# SCH_Solenoid_Door_Lock_using_EM-18_2023-.net
KiCad netlist of a schematic drawn in EasyEDA
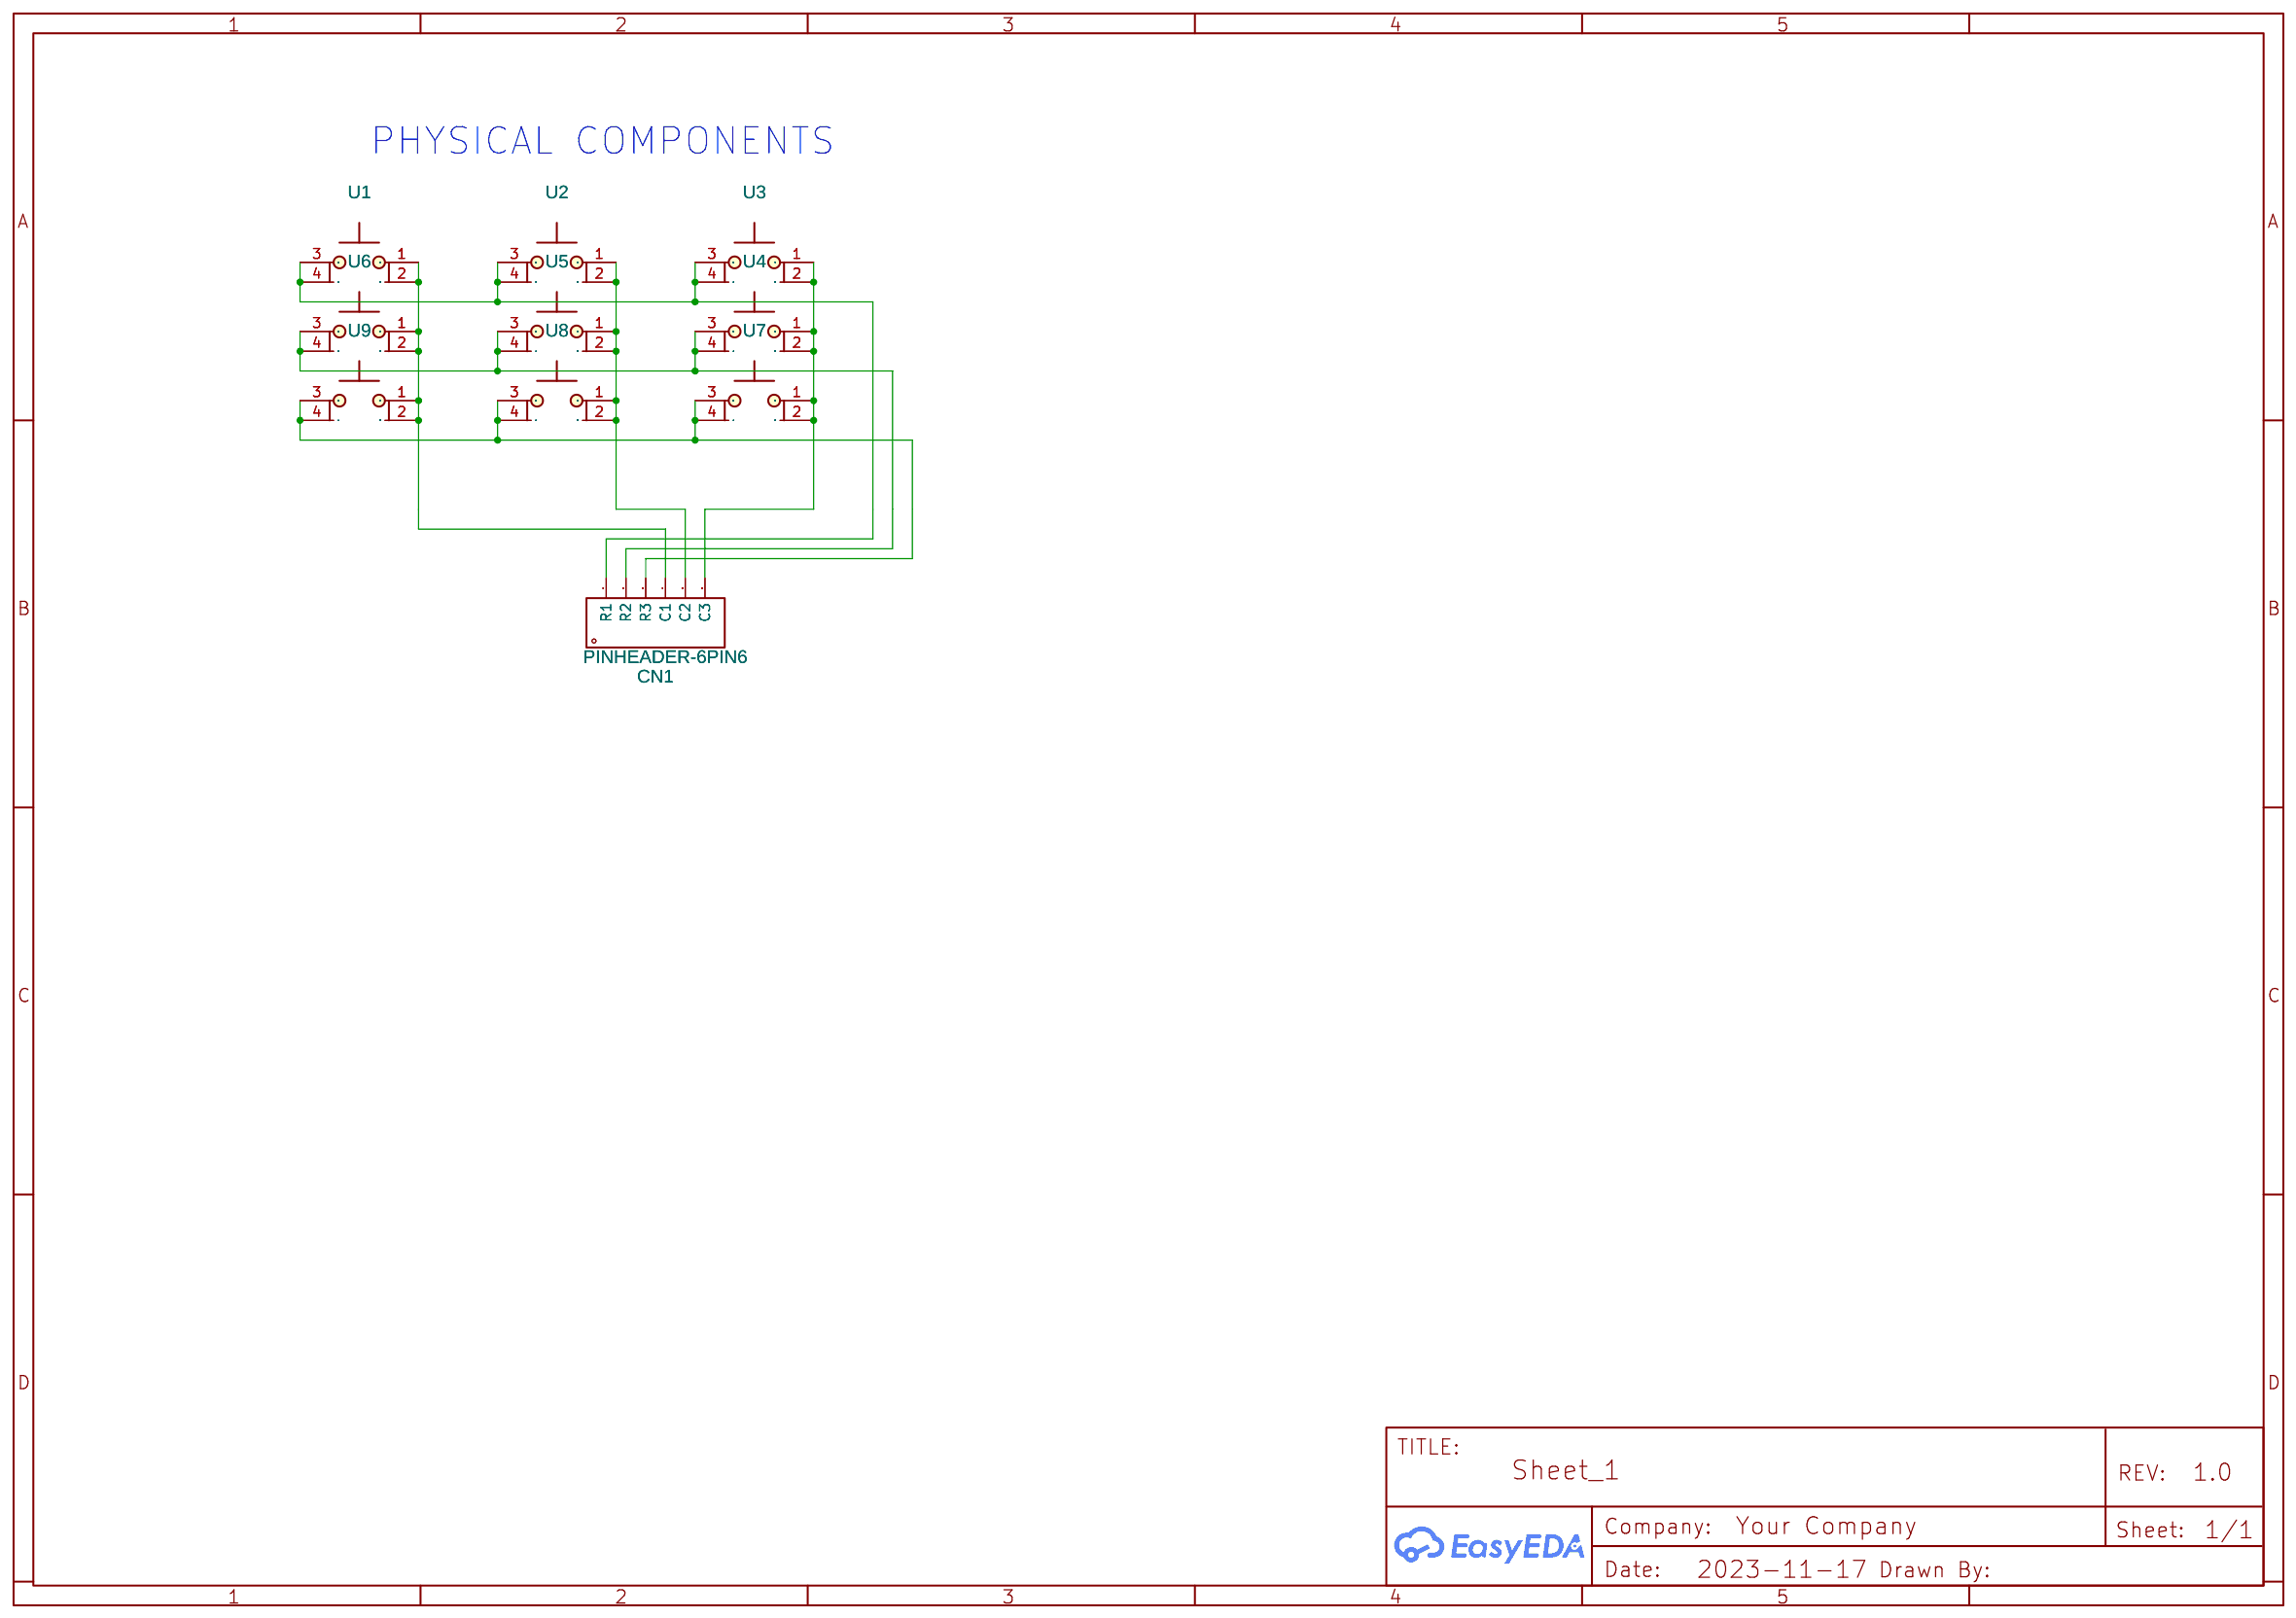
[diagram p0: 3x3 KeyPad]
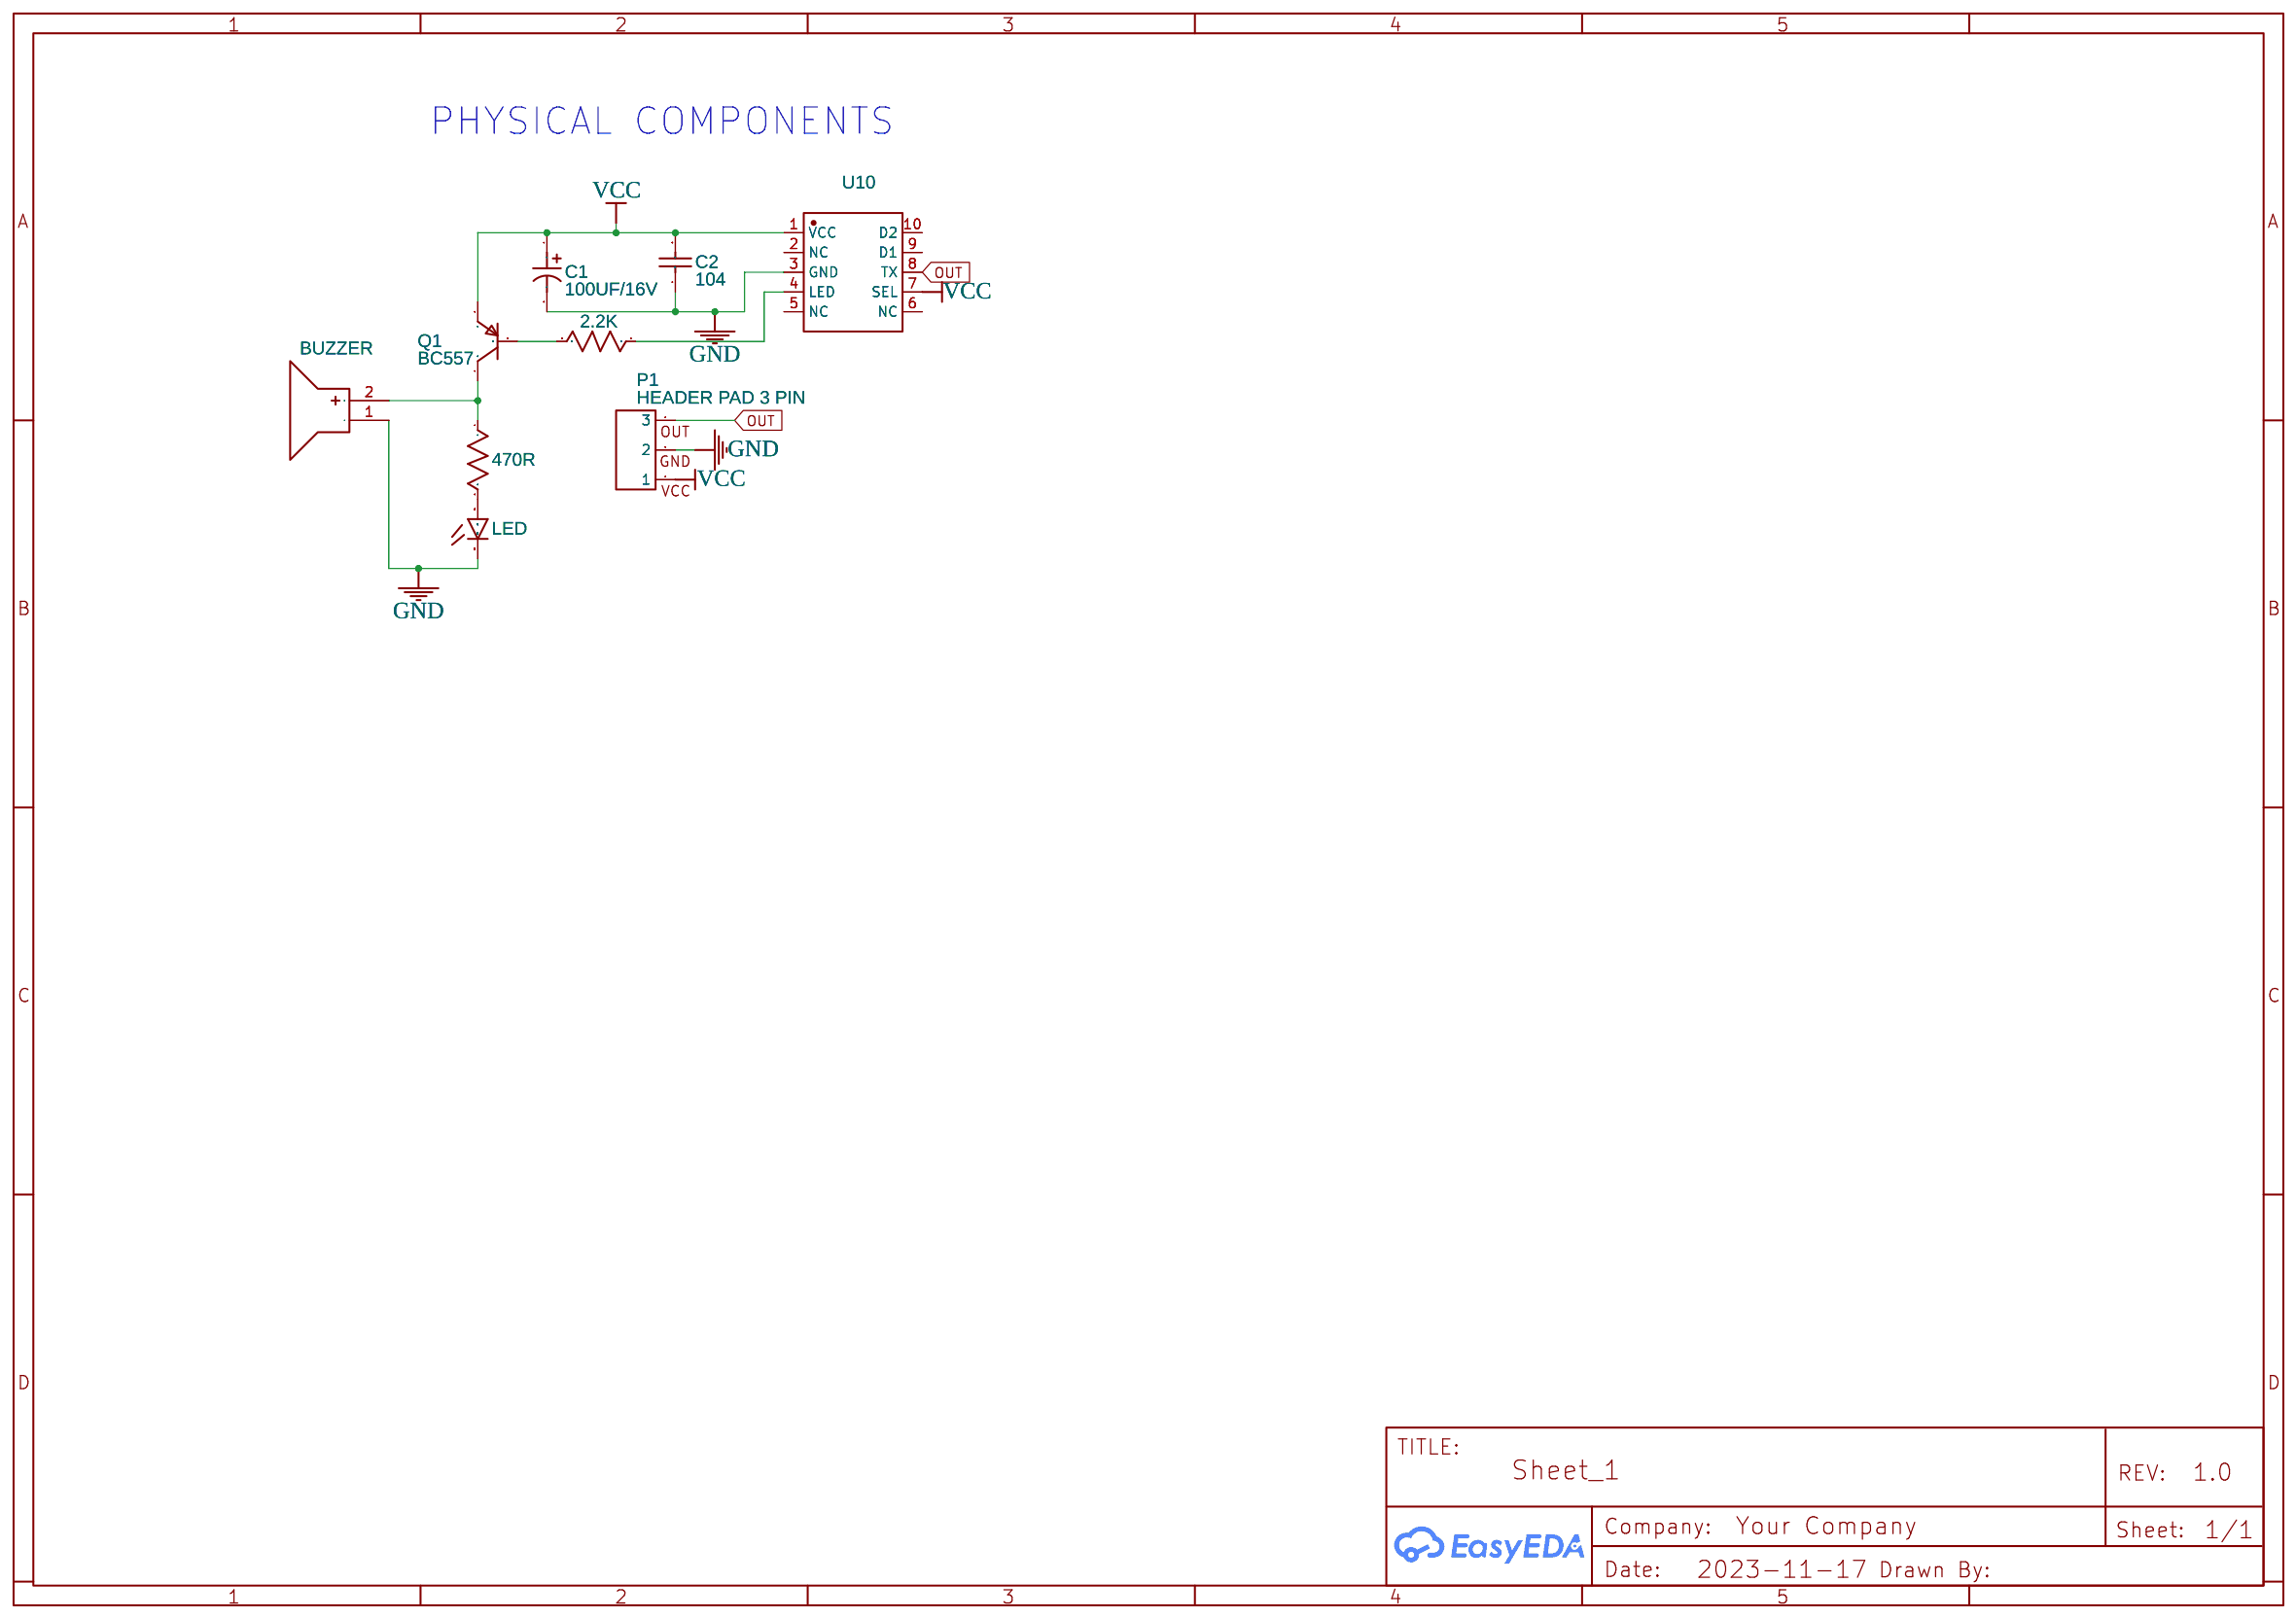
[diagram p1: EM-18 Module]
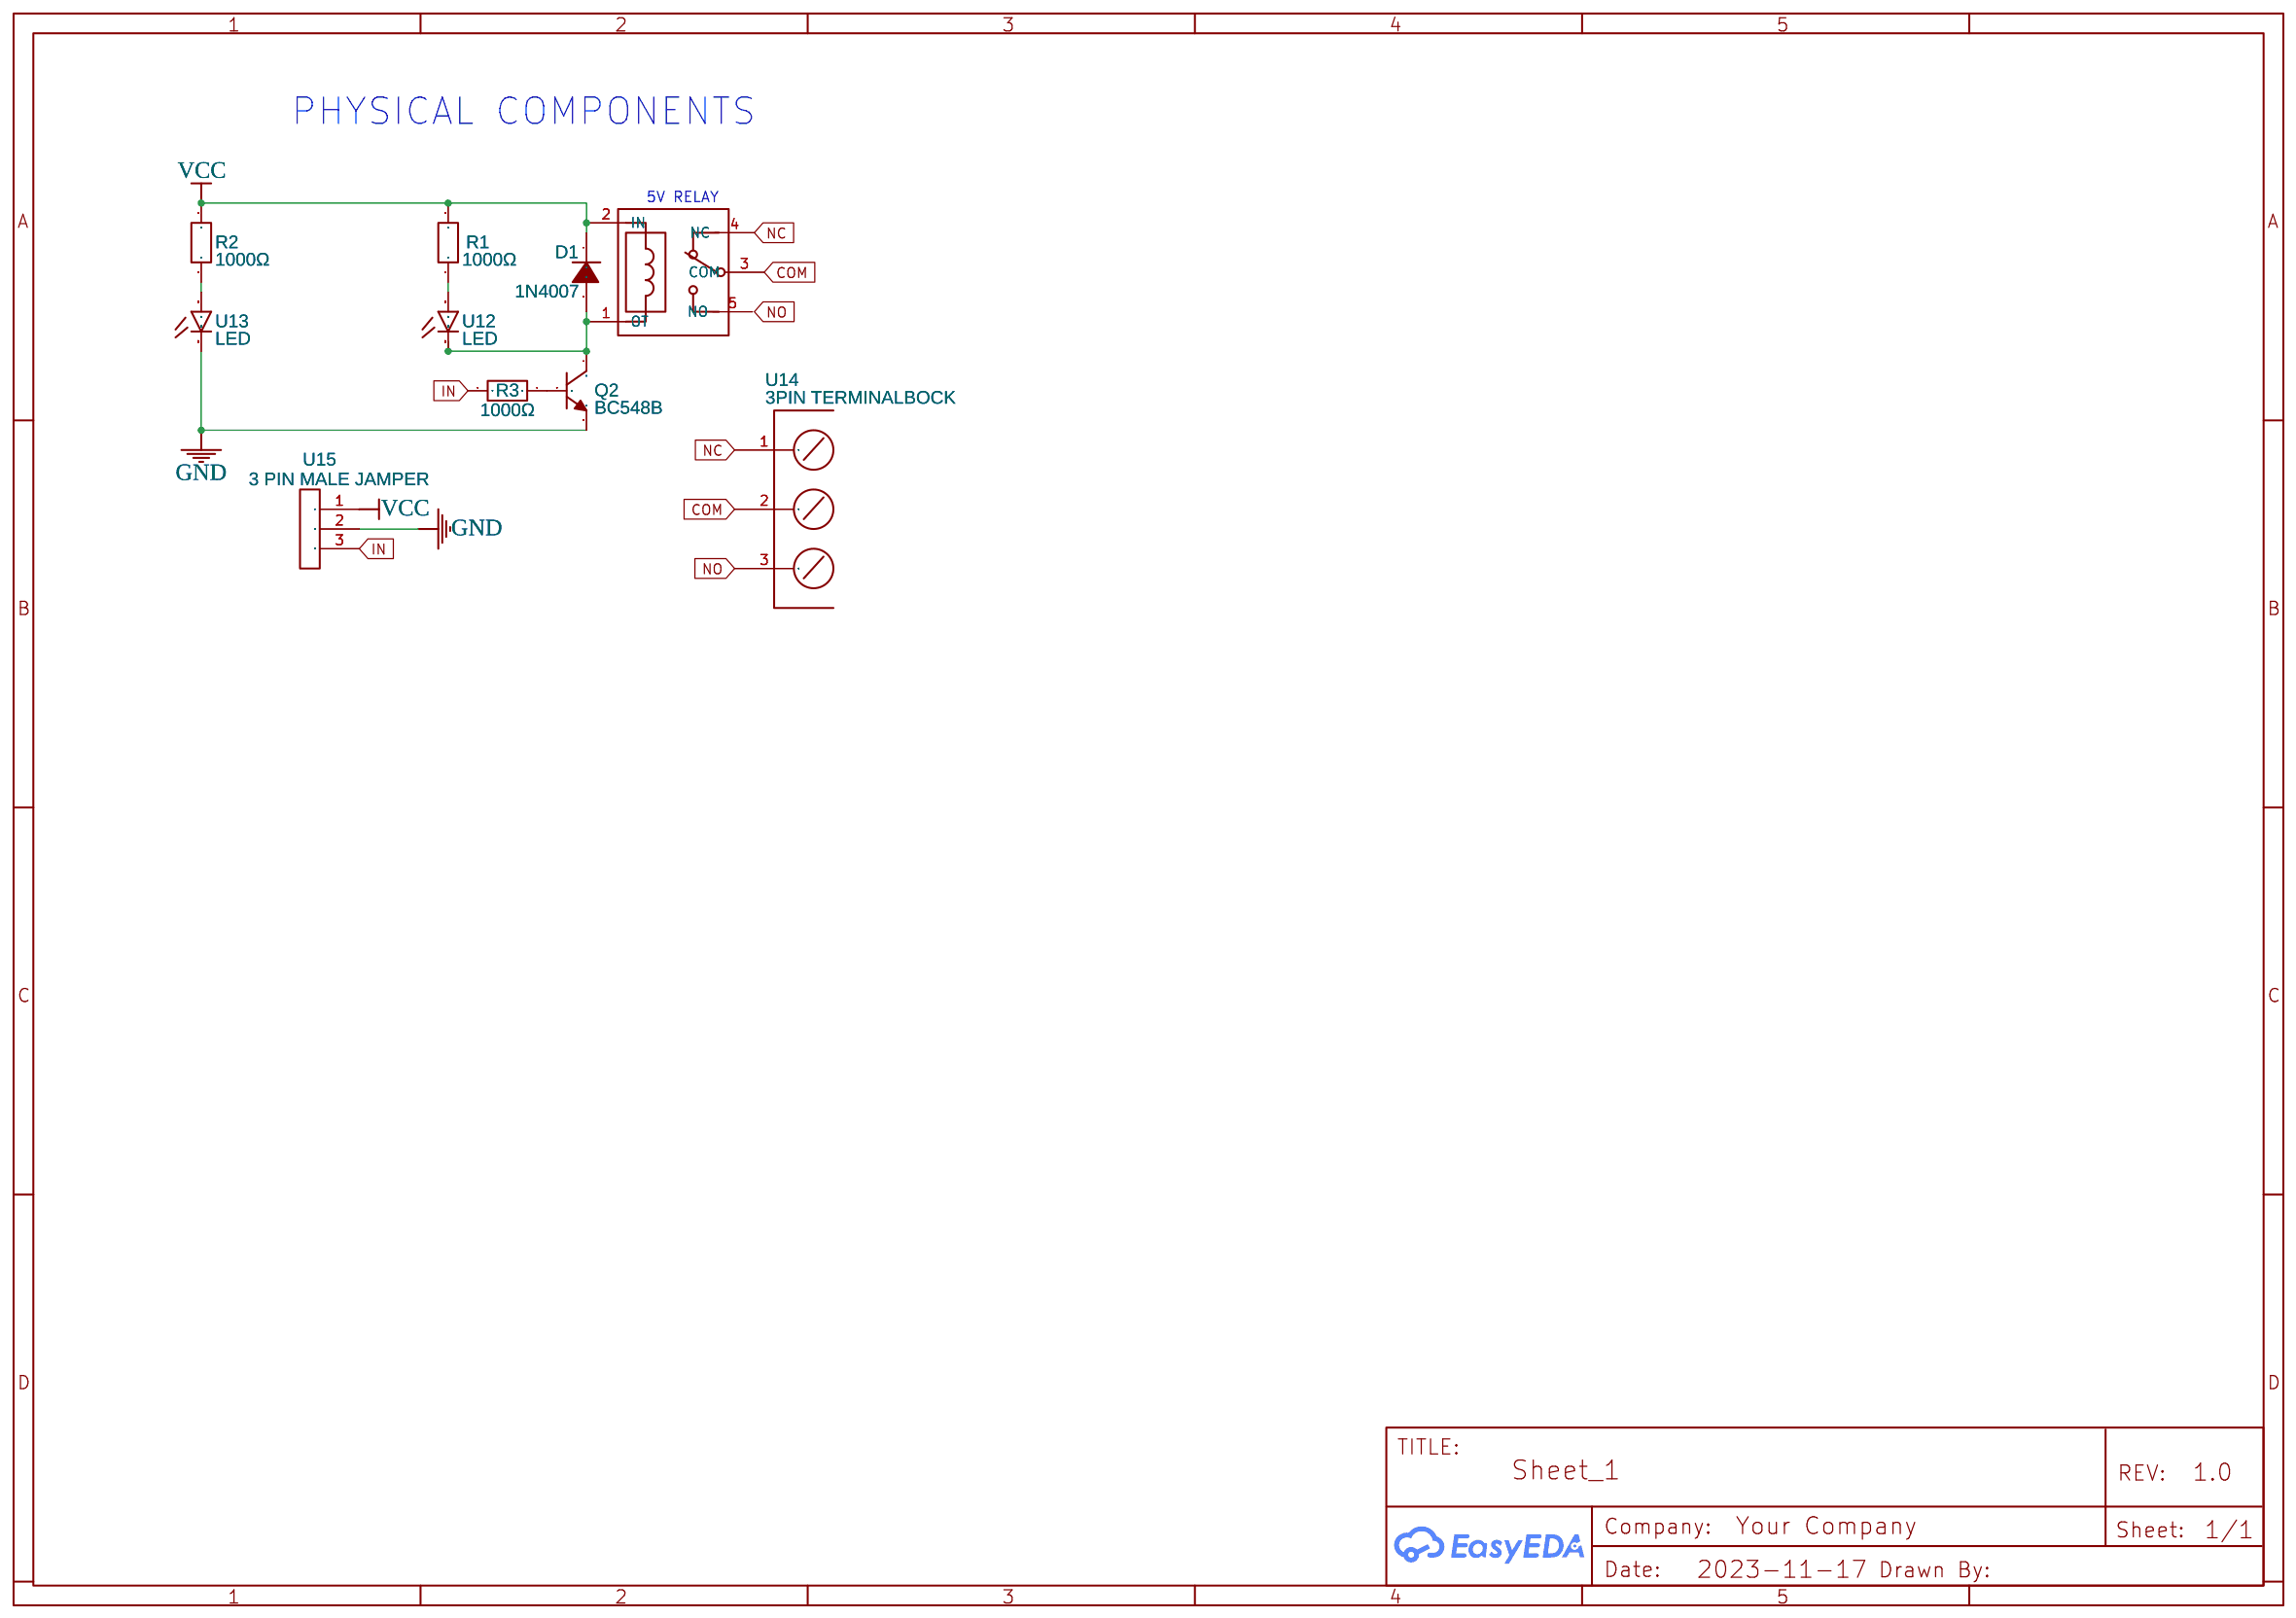
[diagram p2: Relay Module]
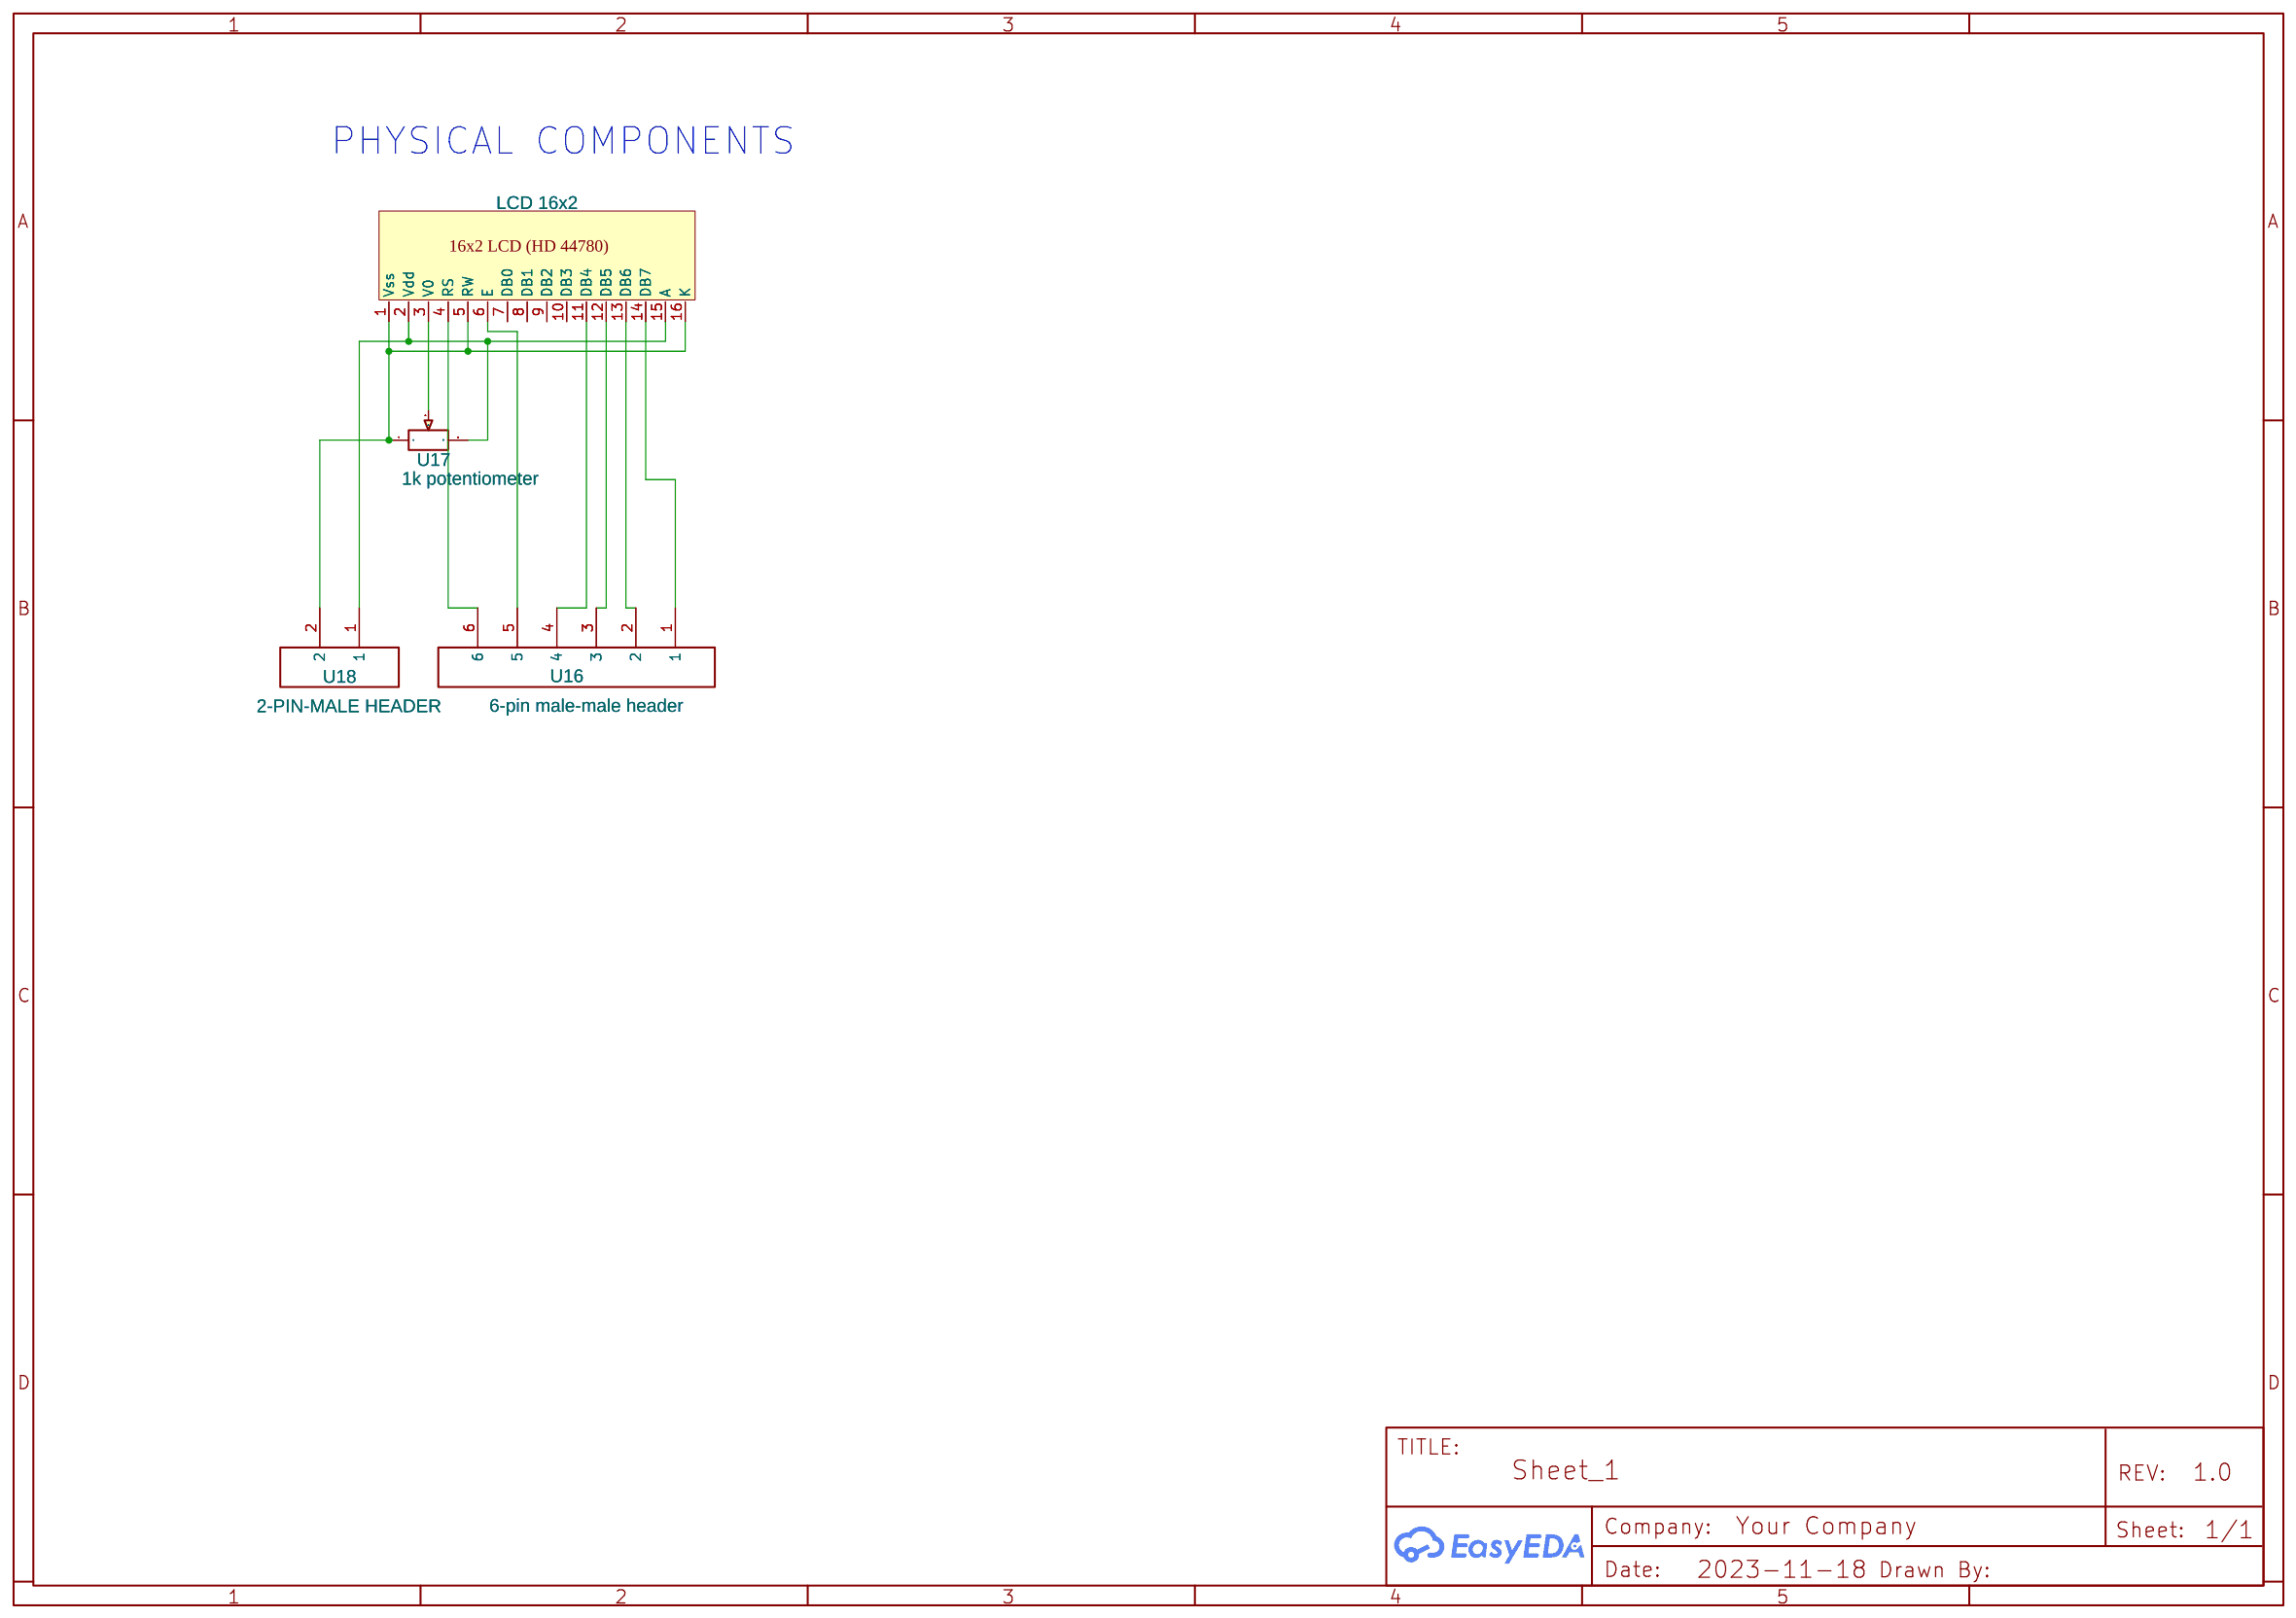
[diagram p3: LCD Display]
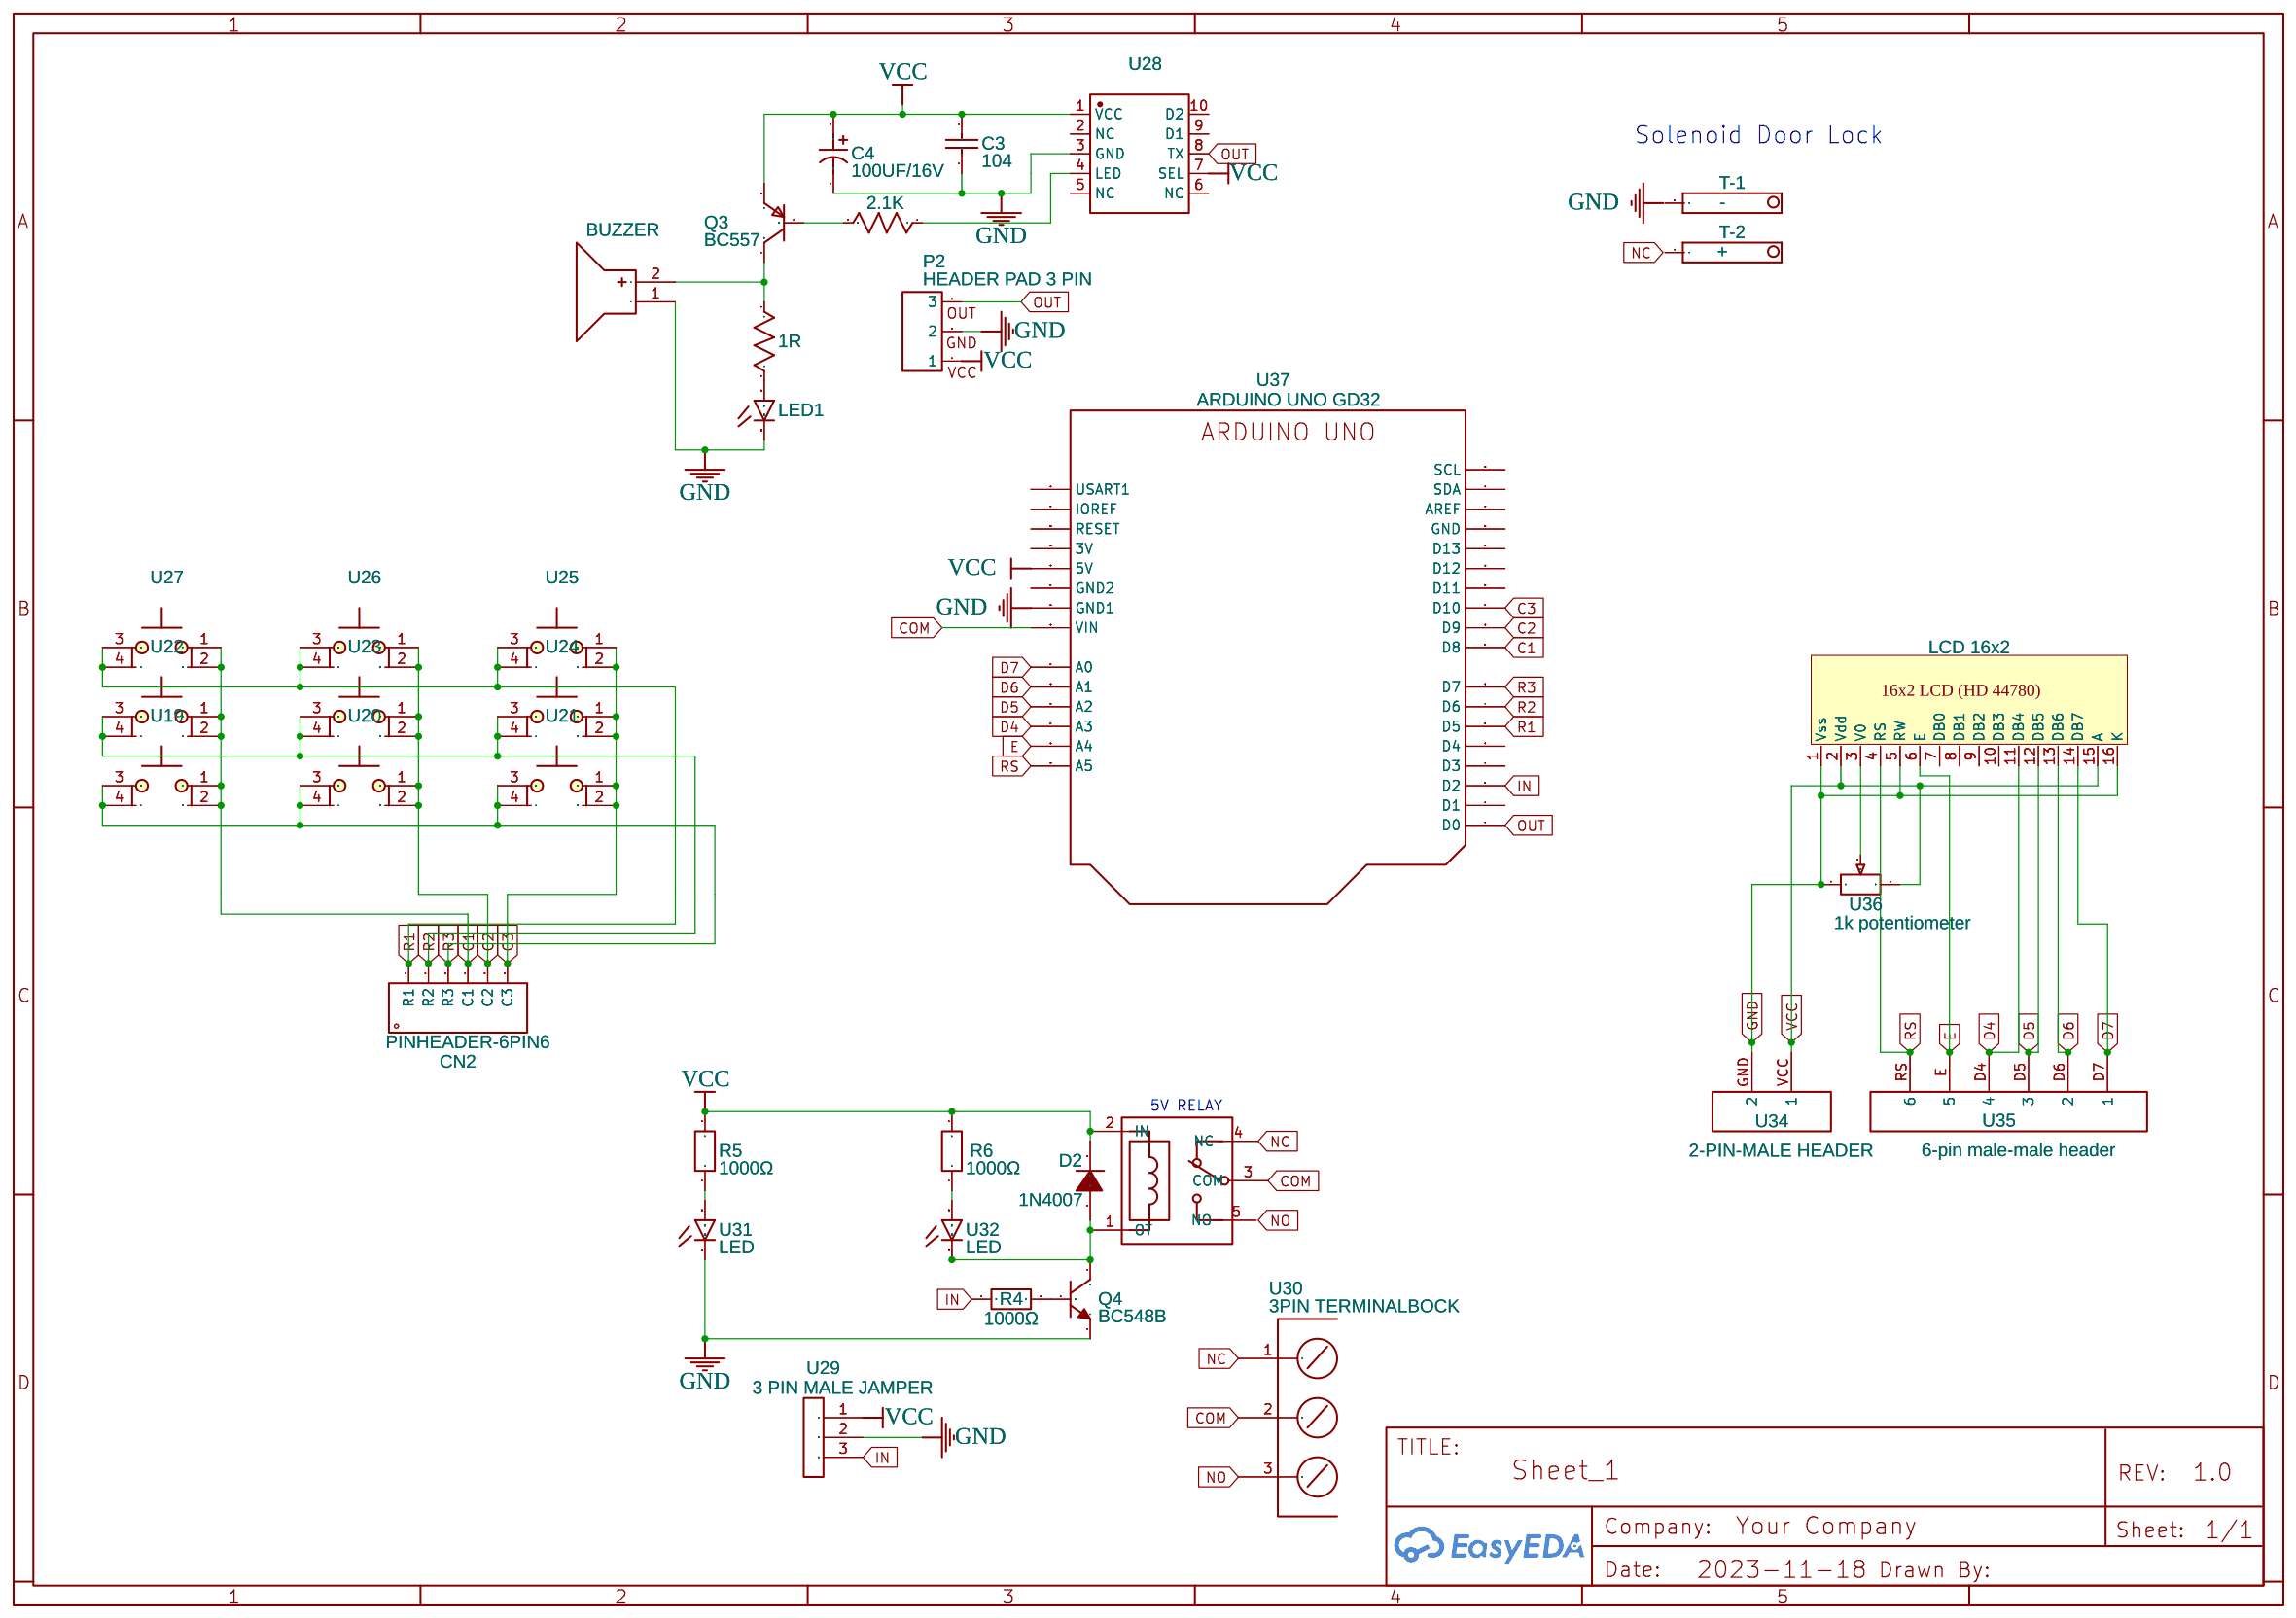
[diagram p4: Final Display]
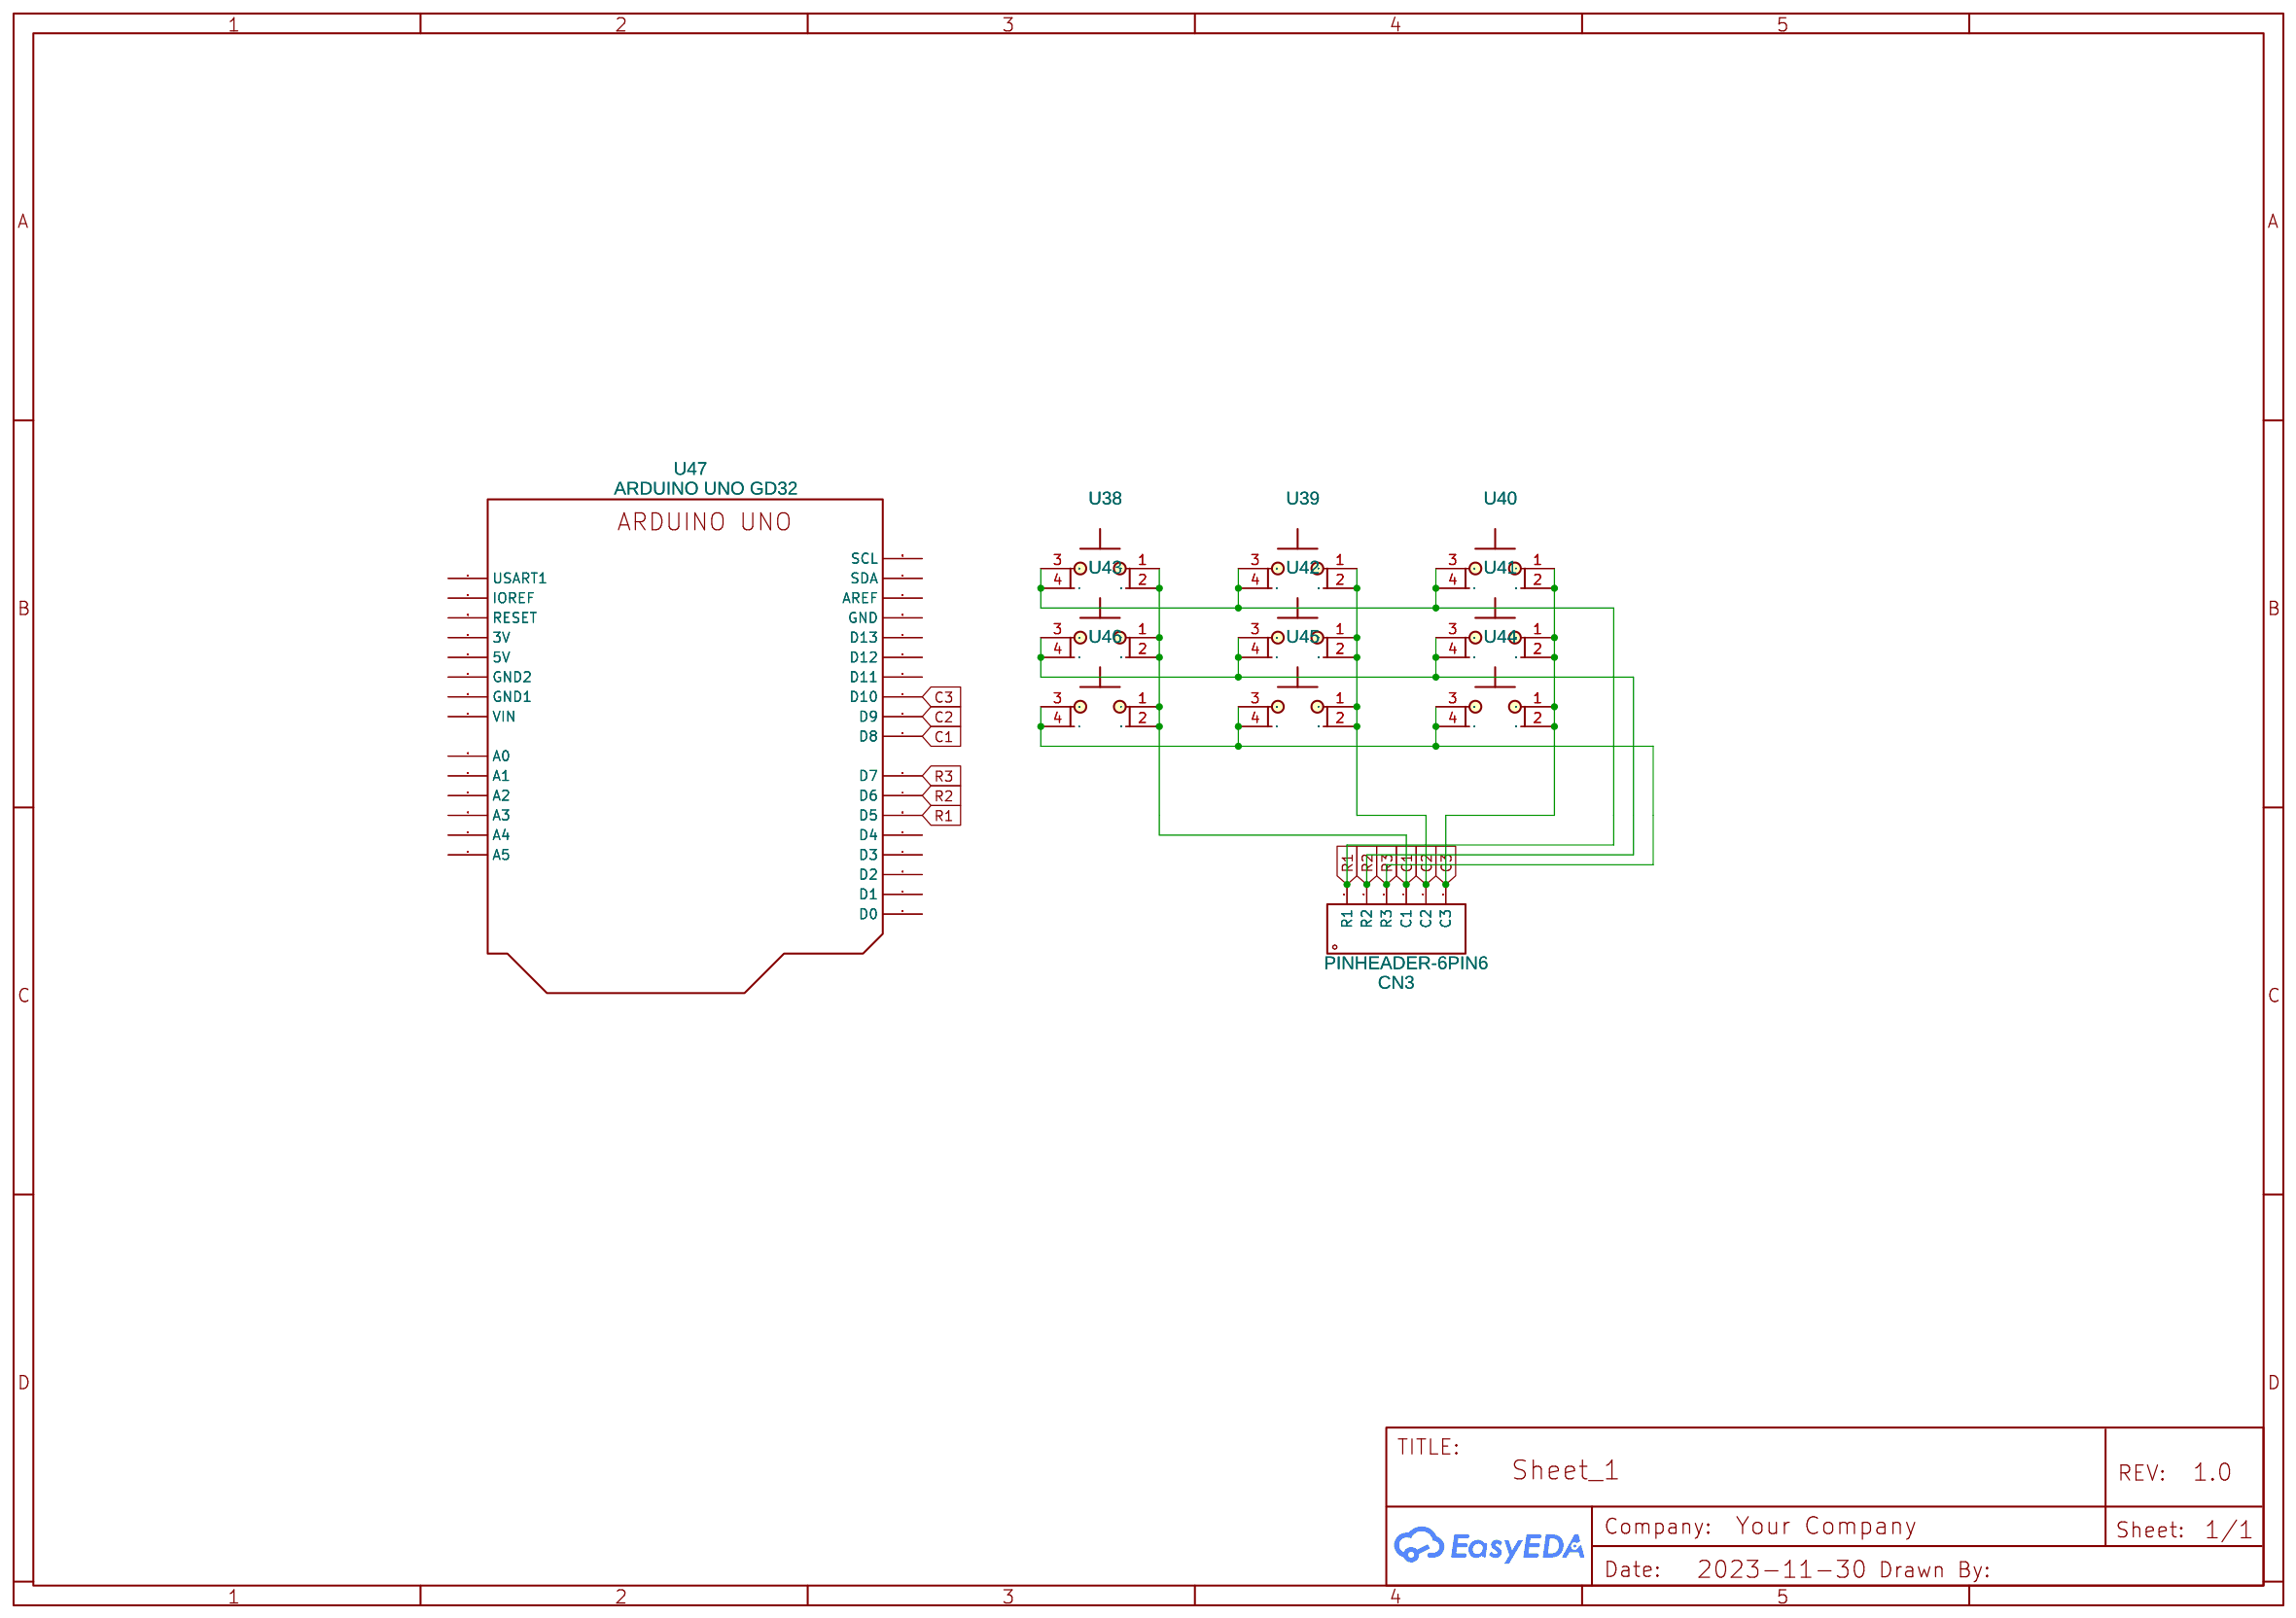
[diagram p5: Arduino_Keypad]
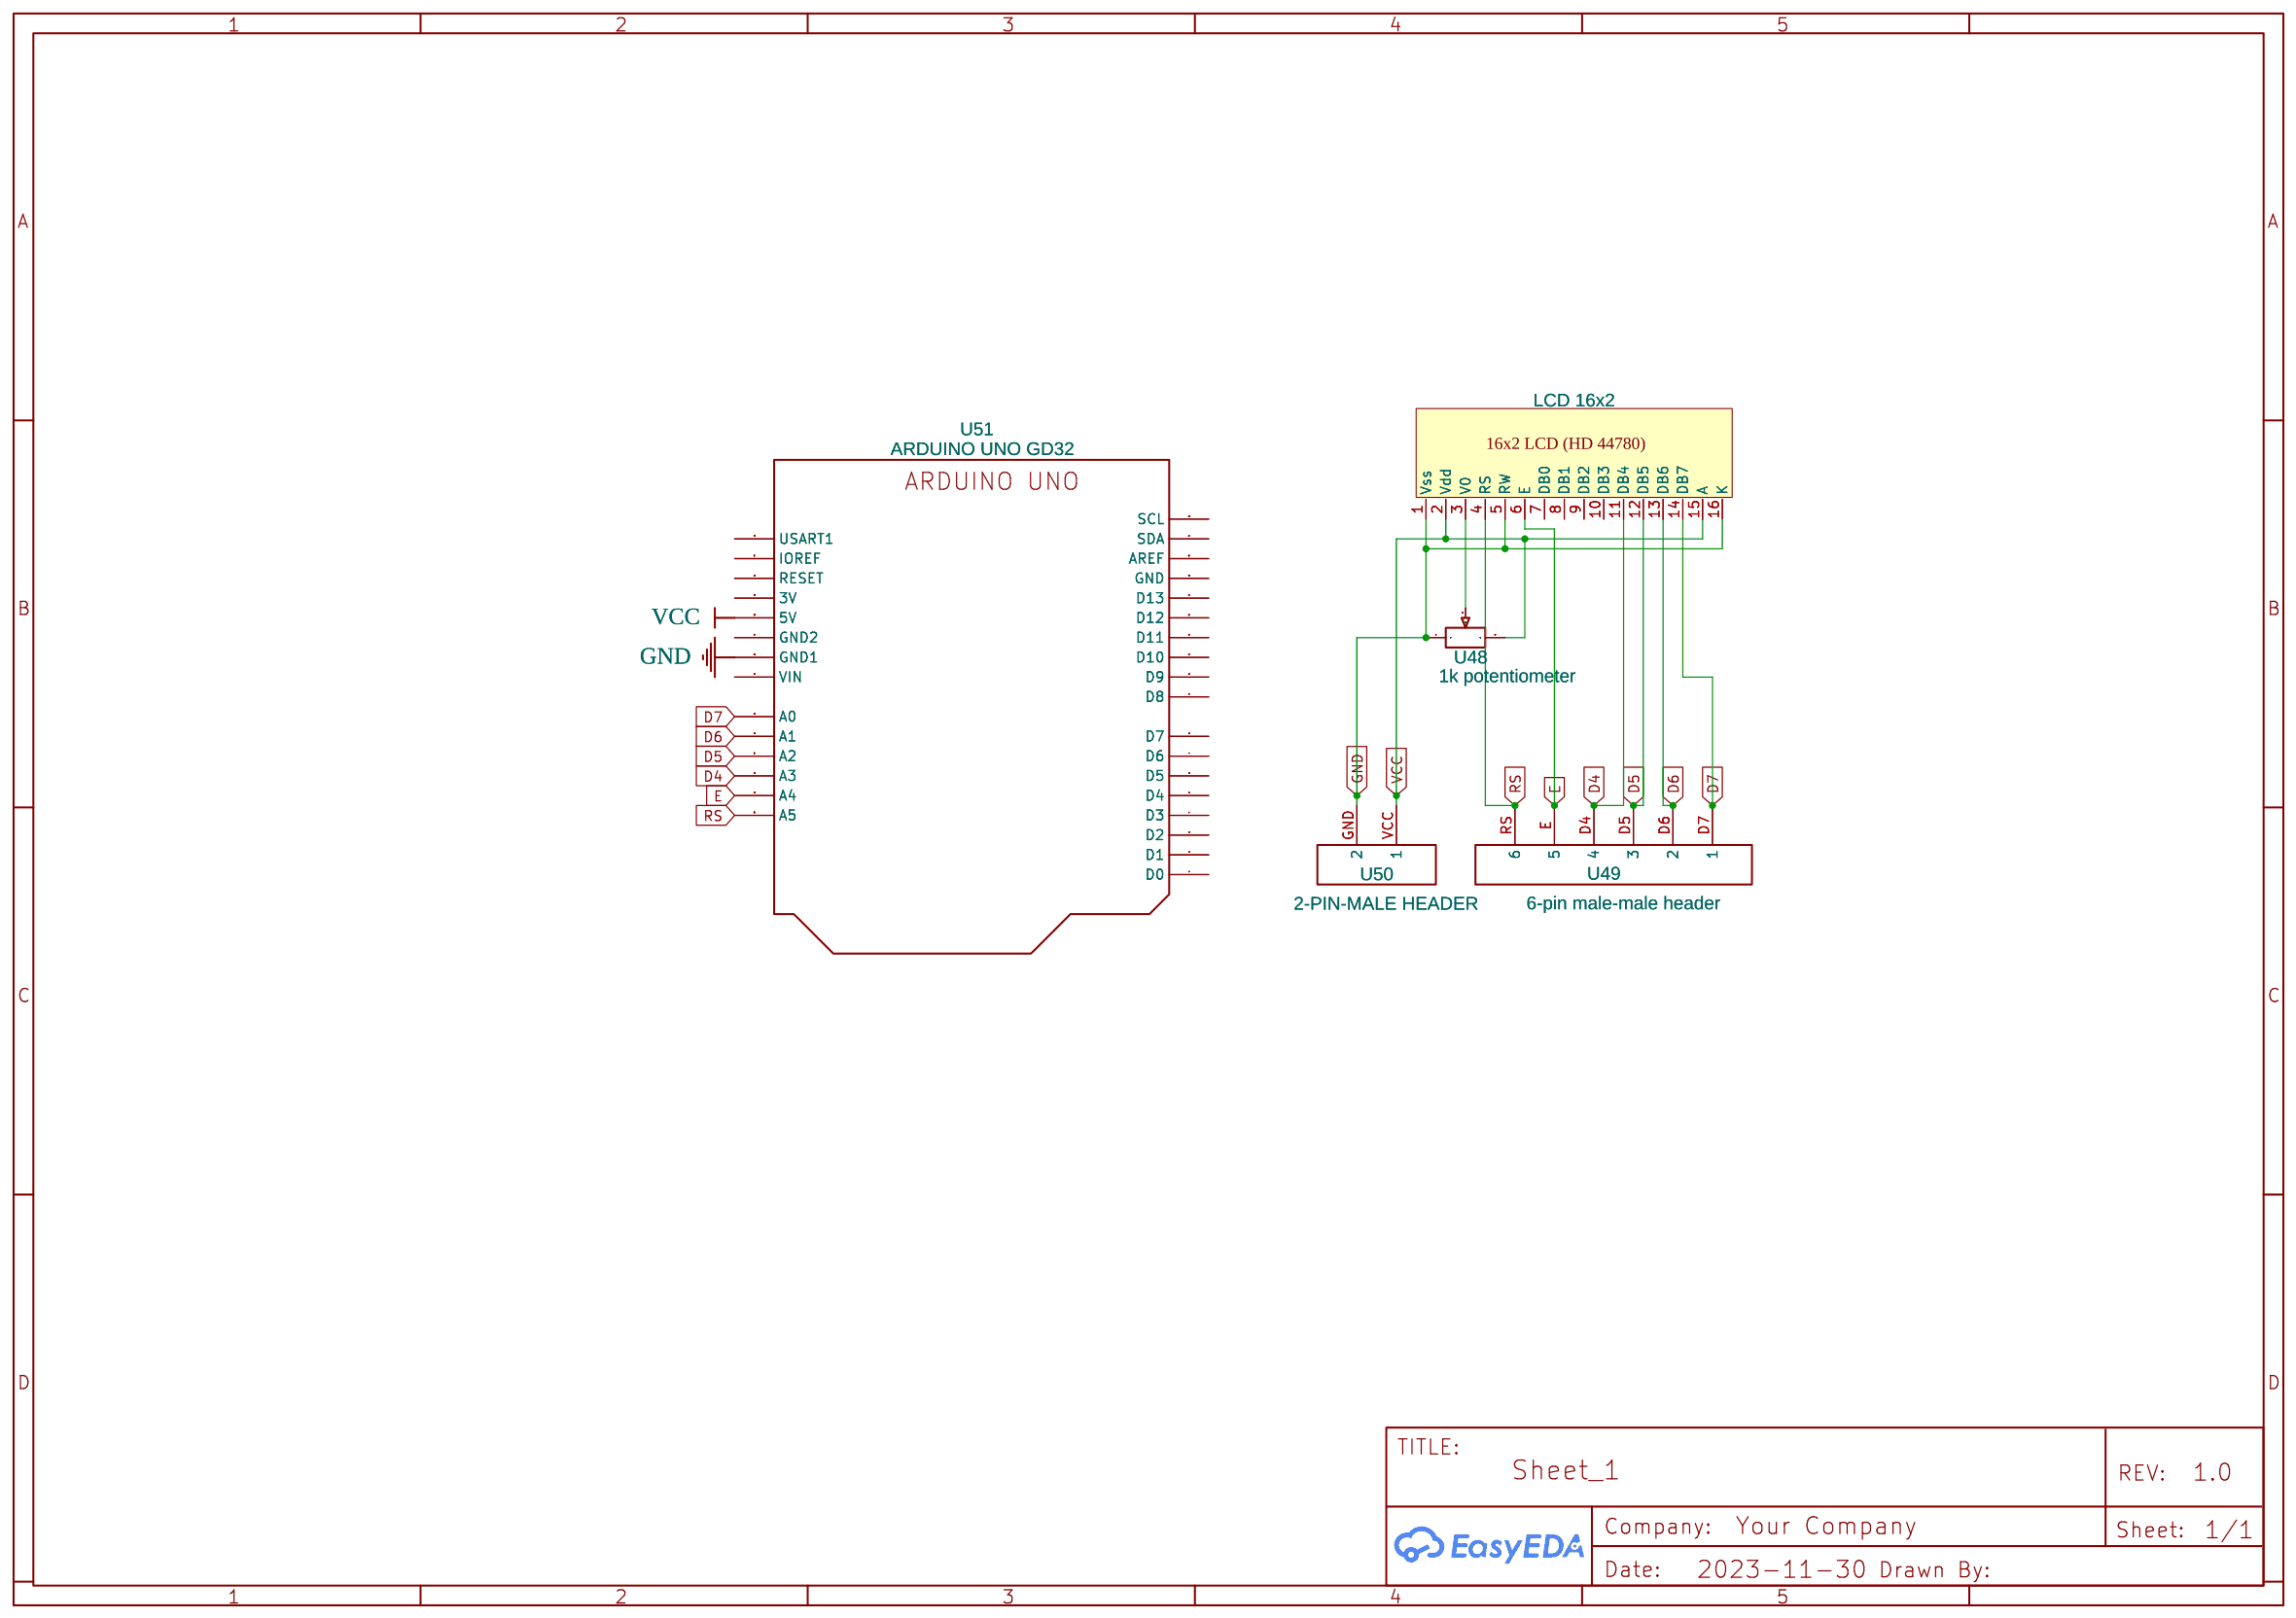
[diagram p6: Arduino_LCD]
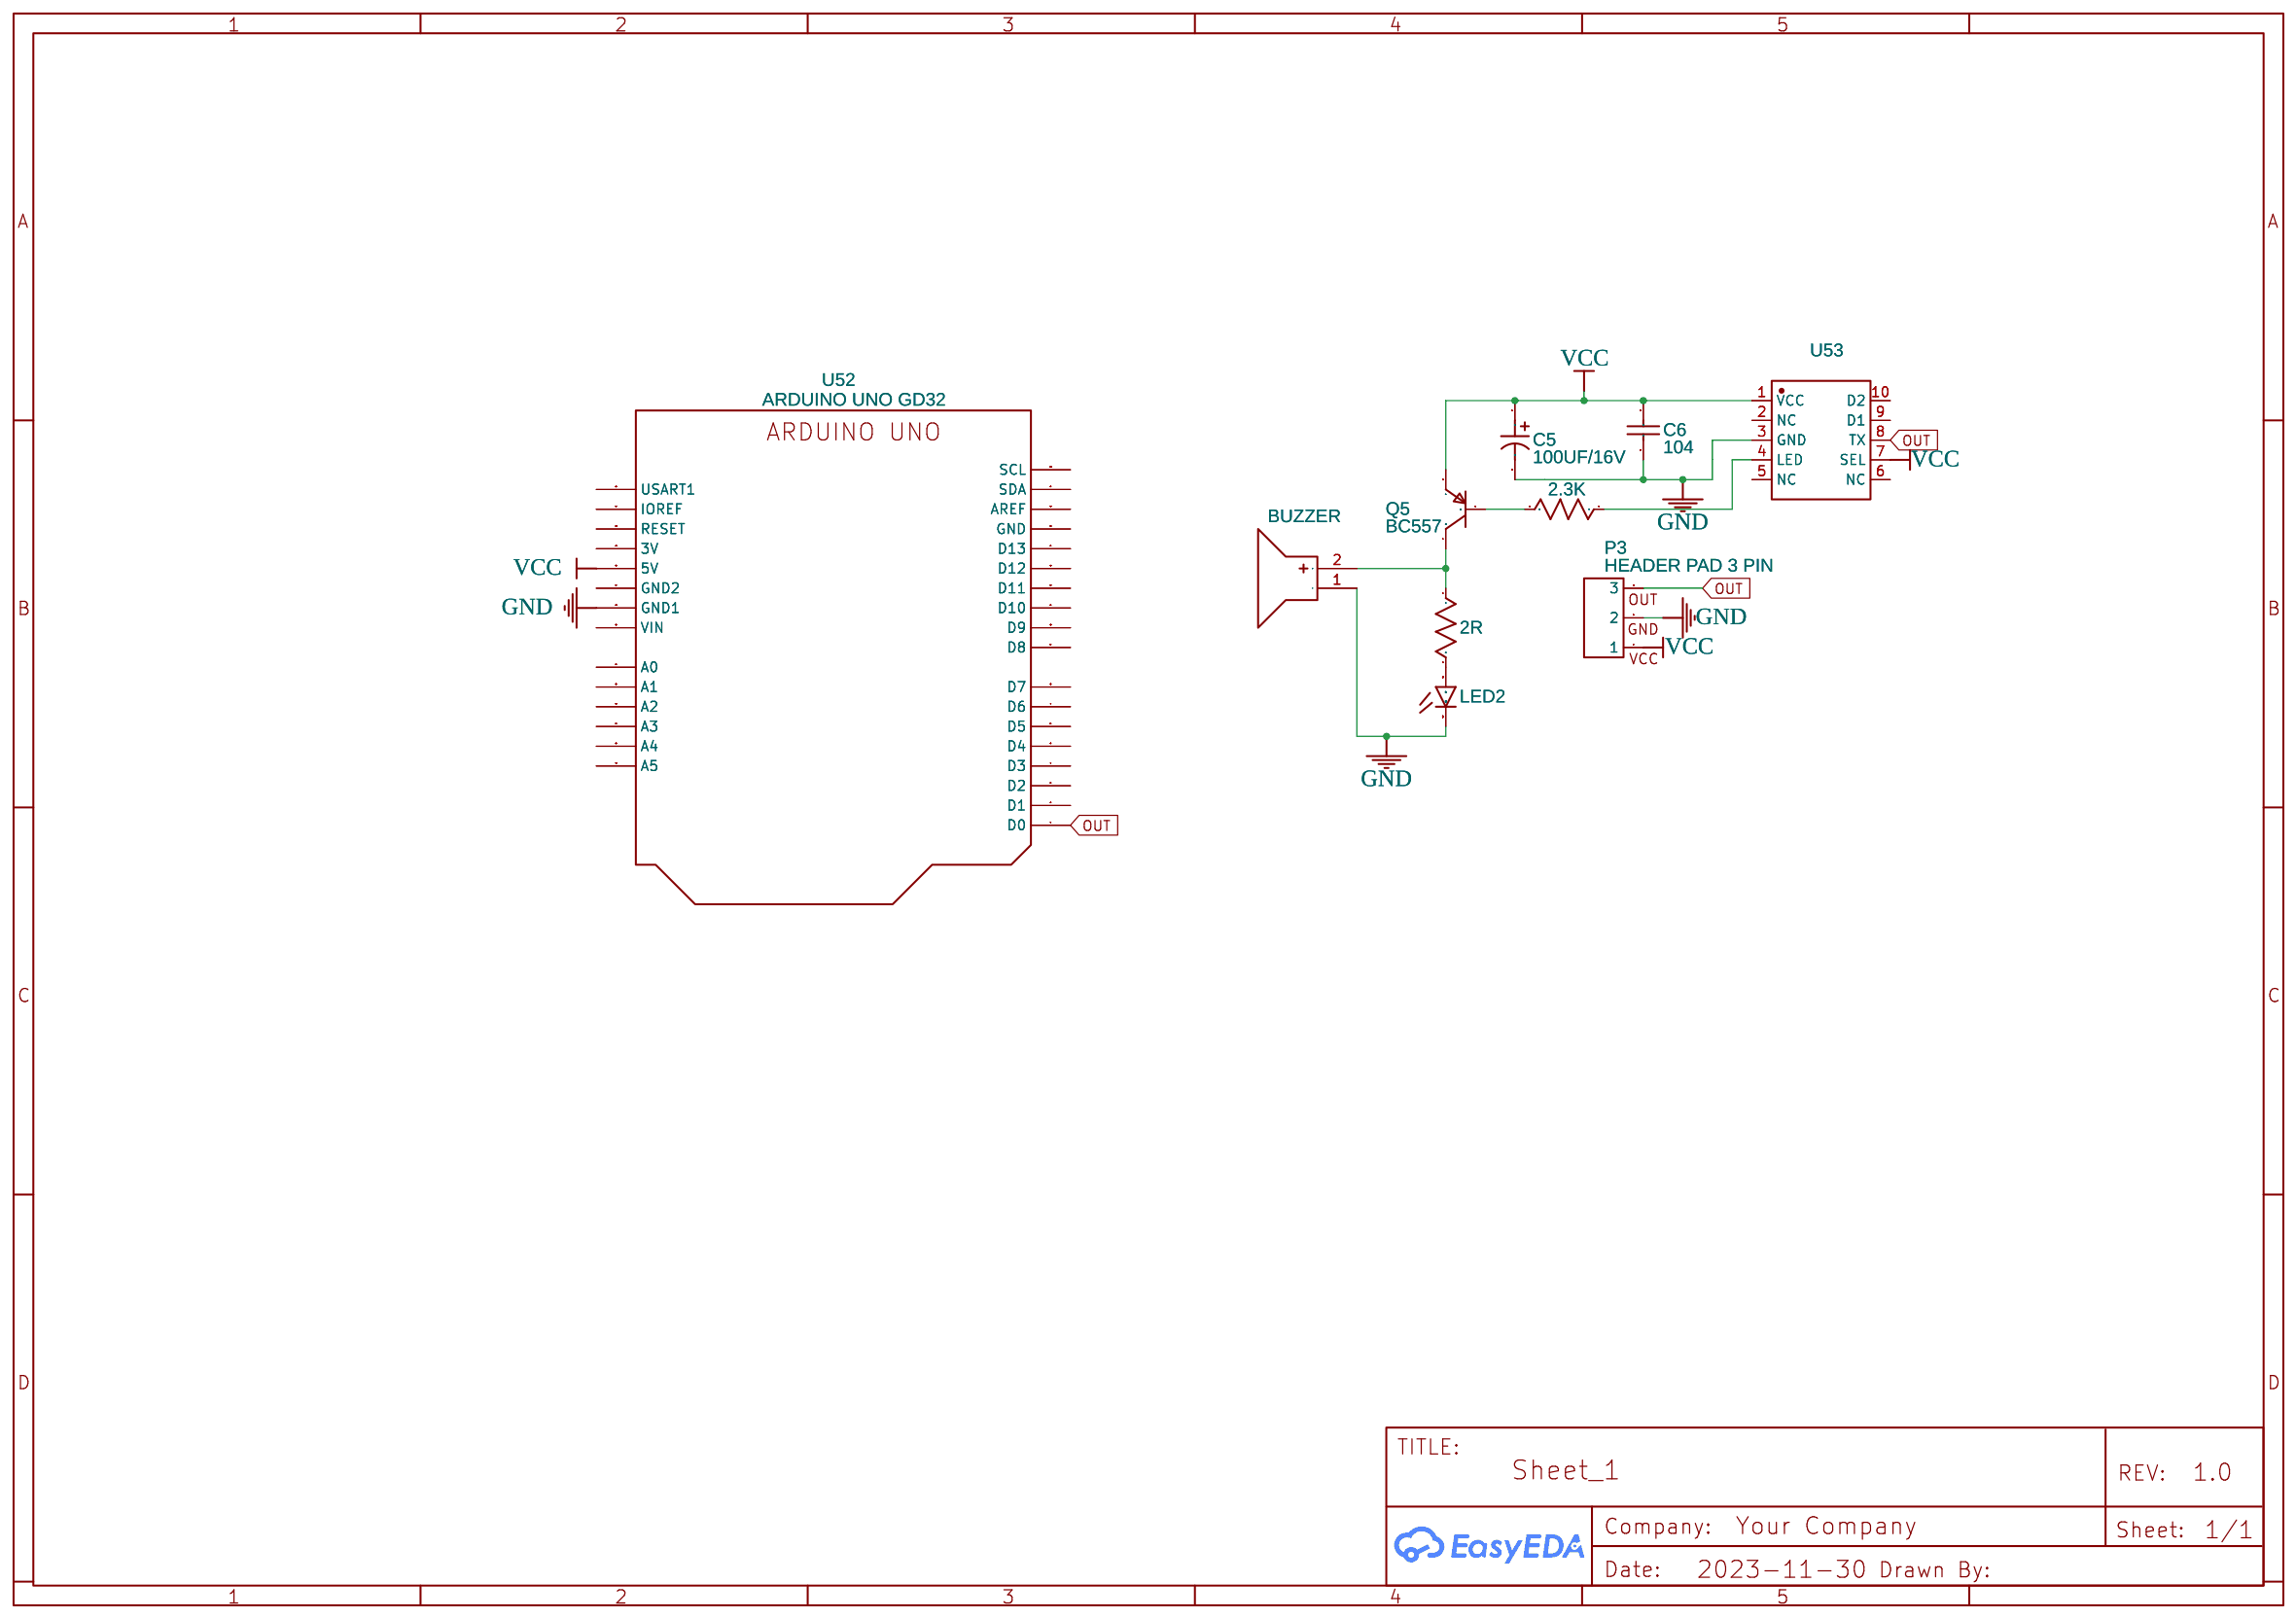
[diagram p7: Arduino_EM-18 Module]
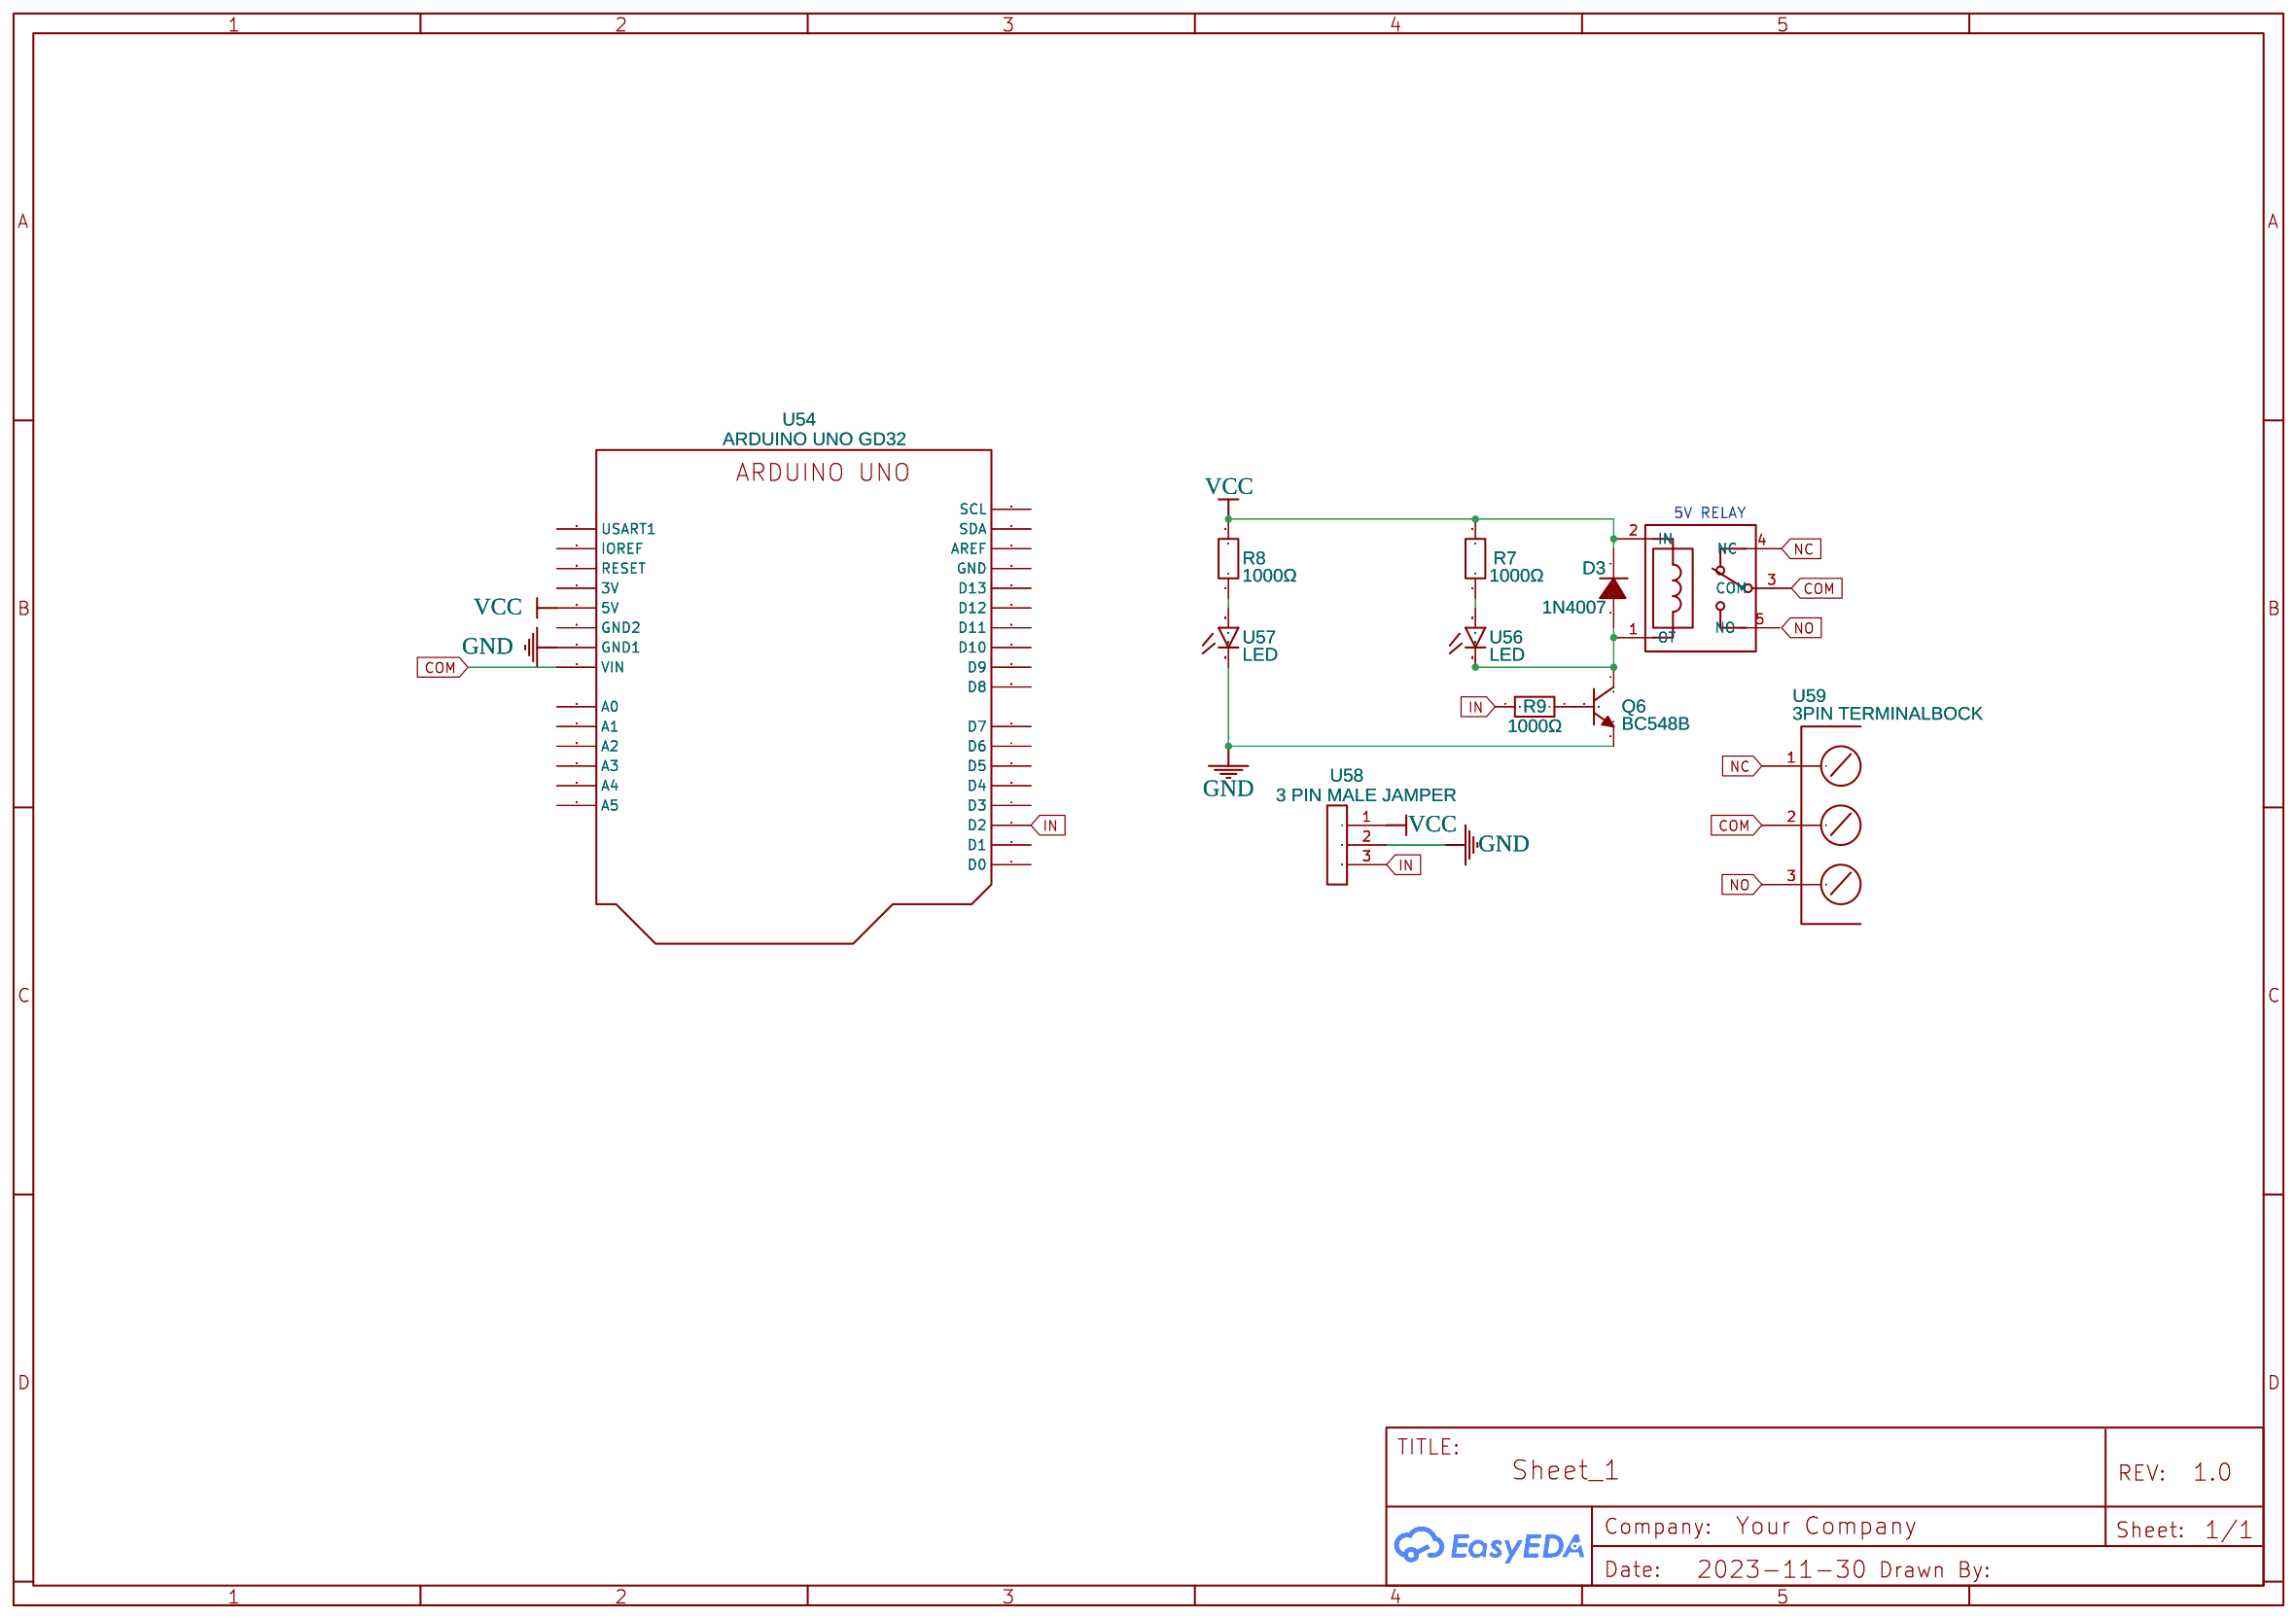
[diagram p8: Arduino_Relay Module]

(export (version "E")
  (design (tool "Eeschema 10.0.6"))
  (components
    (comp (ref "CN1") (value "PINHEADER-6PIN6") (libsource (lib "") (part "PINHEADER-6PIN6")))
    (comp (ref "U1") (value "NO") (libsource (lib "") (part "ESO_SPST_Momentary")))
    (comp (ref "U2") (value "NO") (libsource (lib "") (part "ESO_SPST_Momentary")))
    (comp (ref "U3") (value "NO") (libsource (lib "") (part "ESO_SPST_Momentary")))
    (comp (ref "U4") (value "NO") (libsource (lib "") (part "ESO_SPST_Momentary")))
    (comp (ref "U5") (value "NO") (libsource (lib "") (part "ESO_SPST_Momentary")))
    (comp (ref "U6") (value "NO") (libsource (lib "") (part "ESO_SPST_Momentary")))
    (comp (ref "U7") (value "NO") (libsource (lib "") (part "ESO_SPST_Momentary")))
    (comp (ref "U8") (value "NO") (libsource (lib "") (part "ESO_SPST_Momentary")))
    (comp (ref "U9") (value "NO") (libsource (lib "") (part "ESO_SPST_Momentary")))
    (comp (ref "2.2K")
      (value "~")
      (fields (field (name "Manufacturer") "Huaxing Mechanical-Elec."))
      (libsource (lib "") (part "1/4W-2.2KΩ±1%"))
    )
    (comp (ref "470R")
      (value "~")
      (fields (field (name "Manufacturer") "Huaxing Mechanical-Elec."))
      (libsource (lib "") (part "1/4W-2.2KΩ±1%_1"))
    )
    (comp (ref "BUZZER1")
      (value "BUZZER")
      (fields (field (name "Manufacturer Part") "buzzer"))
      (libsource (lib "") (part "BUZZER"))
    )
    (comp (ref "C1")
      (value "100UF/16V")
      (fields (field (name "Manufacturer Part") "100uF/16V"))
      (libsource (lib "") (part "100UF/16V"))
    )
    (comp (ref "C2")
      (value "104")
      (fields
        (field (name "Manufacturer Part") "Suppression Capacitor222M/250V")
        (field (name "Manufacturer") "ReliaPro")
      )
      (libsource (lib "") (part "104nf"))
    )
    (comp (ref "LED") (value "~") (libsource (lib "") (part "-LED")))
    (comp (ref "P1")
      (value "HEADER PAD 3 PIN")
      (fields
        (field (name "Manufacturer Part") "Female headerHDR1X8-2.54")
        (field (name "Manufacturer") "BOOMELE")
      )
      (libsource (lib "") (part "HEADER PAD 3 PIN"))
    )
    (comp (ref "Q1")
      (value "BC557")
      (fields (field (name "Manufacturer") "CJ(江苏长电/长晶)"))
      (libsource (lib "") (part "BC557"))
    )
    (comp (ref "U10") (value "~") (libsource (lib "") (part "EM-18")))
    (comp (ref "D1")
      (value "1N4007")
      (fields (field (name "Manufacturer") "ST(先科)"))
      (libsource (lib "") (part "1N4007"))
    )
    (comp (ref "Q2")
      (value "BC548B")
      (fields (field (name "Manufacturer Part") "BC548") (field (name "Manufacturer") "CJ(江苏长电/长晶)"))
      (libsource (lib "") (part "BC548B"))
    )
    (comp (ref "R1") (value "1000Ω") (libsource (lib "") (part "330Ω RESISTANCE_1")))
    (comp (ref "R2") (value "1000Ω") (libsource (lib "") (part "330Ω RESISTANCE_1")))
    (comp (ref "R3") (value "1000Ω") (libsource (lib "") (part "330Ω RESISTANCE")))
    (comp (ref "U11")
      (value "~")
      (fields (field (name "Manufacturer Part") "SRD-05VDC-SL-C") (field (name "Manufacturer") "松乐"))
      (libsource (lib "") (part "SRD-05VDC-SL-C"))
    )
    (comp (ref "U12") (value "LED") (libsource (lib "") (part "-LED")))
    (comp (ref "U13") (value "LED") (libsource (lib "") (part "-LED")))
    (comp (ref "U14") (value "3PIN TERMINALBOCK") (libsource (lib "") (part "3PIN TERMINALBOCK")))
    (comp (ref "U15")
      (value "3 PIN MALE JAMPER")
      (fields (field (name "Manufacturer Part") "1x3 pin header") (field (name "Manufacturer") "NA"))
      (libsource (lib "") (part "3 PIN MALE JAMPER"))
    )
    (comp (ref "LCD1") (value "LCD 16x2") (libsource (lib "") (part "LCD 16x2")))
    (comp (ref "U16")
      (value "6-pin male-male header")
      (fields (field (name "Manufacturer Part") "87224-5") (field (name "Manufacturer") "TE Connectivity"))
      (libsource (lib "") (part "6-pin male-male header"))
    )
    (comp (ref "U17") (value "1k potentiometer") (libsource (lib "") (part "Pot_blue")))
    (comp (ref "U18")
      (value "2-PIN-MALE HEADER")
      (fields (field (name "Manufacturer Part") "87224-5") (field (name "Manufacturer") "TE Connectivity"))
      (libsource (lib "") (part "2-PIN-MALE HEADER"))
    )
    (comp (ref "+") (value "T-2") (libsource (lib "") (part "TERMINAL-BLOCK-3.5MM-2-PIN-LONG-PAD_1")))
    (comp (ref "-") (value "T-1") (libsource (lib "") (part "TERMINAL-BLOCK-3.5MM-2-PIN-LONG-PAD")))
    (comp (ref "1R")
      (value "NO")
      (fields (field (name "Manufacturer") "Huaxing Mechanical-Elec."))
      (libsource (lib "") (part "1/4W-2.2KΩ±1%"))
    )
    (comp (ref "2.1K")
      (value "NO")
      (fields (field (name "Manufacturer") "Huaxing Mechanical-Elec."))
      (libsource (lib "") (part "1/4W-2.2KΩ±1%_1"))
    )
    (comp (ref "BUZZER2")
      (value "BUZZER")
      (fields (field (name "Manufacturer Part") "buzzer"))
      (libsource (lib "") (part "BUZZER"))
    )
    (comp (ref "C3")
      (value "104")
      (fields
        (field (name "Manufacturer Part") "Suppression Capacitor222M/250V")
        (field (name "Manufacturer") "ReliaPro")
      )
      (libsource (lib "") (part "104nf"))
    )
    (comp (ref "C4")
      (value "100UF/16V")
      (fields (field (name "Manufacturer Part") "100uF/16V"))
      (libsource (lib "") (part "100UF/16V"))
    )
    (comp (ref "CN2") (value "PINHEADER-6PIN6") (libsource (lib "") (part "PINHEADER-6PIN6")))
    (comp (ref "D2")
      (value "1N4007")
      (fields (field (name "Manufacturer") "ST(先科)"))
      (libsource (lib "") (part "1N4007"))
    )
    (comp (ref "LCD2") (value "LCD 16x2") (libsource (lib "") (part "LCD 16x2")))
    (comp (ref "LED1") (value "NO") (libsource (lib "") (part "-LED_1")))
    (comp (ref "P2")
      (value "HEADER PAD 3 PIN")
      (fields
        (field (name "Manufacturer Part") "Female headerHDR1X8-2.54")
        (field (name "Manufacturer") "BOOMELE")
      )
      (libsource (lib "") (part "HEADER PAD 3 PIN"))
    )
    (comp (ref "Q3")
      (value "BC557")
      (fields (field (name "Manufacturer") "CJ(江苏长电/长晶)"))
      (libsource (lib "") (part "BC557"))
    )
    (comp (ref "Q4")
      (value "BC548B")
      (fields (field (name "Manufacturer Part") "BC548") (field (name "Manufacturer") "CJ(江苏长电/长晶)"))
      (libsource (lib "") (part "BC548B"))
    )
    (comp (ref "R4") (value "1000Ω") (libsource (lib "") (part "330Ω RESISTANCE_1")))
    (comp (ref "R5") (value "1000Ω") (libsource (lib "") (part "330Ω RESISTANCE")))
    (comp (ref "R6") (value "1000Ω") (libsource (lib "") (part "330Ω RESISTANCE")))
    (comp (ref "U19") (value "NO") (libsource (lib "") (part "ESO_SPST_Momentary")))
    (comp (ref "U20") (value "NO") (libsource (lib "") (part "ESO_SPST_Momentary")))
    (comp (ref "U21") (value "NO") (libsource (lib "") (part "ESO_SPST_Momentary")))
    (comp (ref "U22") (value "NO") (libsource (lib "") (part "ESO_SPST_Momentary")))
    (comp (ref "U23") (value "NO") (libsource (lib "") (part "ESO_SPST_Momentary")))
    (comp (ref "U24") (value "NO") (libsource (lib "") (part "ESO_SPST_Momentary")))
    (comp (ref "U25") (value "NO") (libsource (lib "") (part "ESO_SPST_Momentary")))
    (comp (ref "U26") (value "NO") (libsource (lib "") (part "ESO_SPST_Momentary")))
    (comp (ref "U27") (value "NO") (libsource (lib "") (part "ESO_SPST_Momentary")))
    (comp (ref "U28") (value "NO") (libsource (lib "") (part "EM-18")))
    (comp (ref "U29")
      (value "3 PIN MALE JAMPER")
      (fields (field (name "Manufacturer Part") "1x3 pin header") (field (name "Manufacturer") "NA"))
      (libsource (lib "") (part "3 PIN MALE JAMPER"))
    )
    (comp (ref "U30") (value "3PIN TERMINALBOCK") (libsource (lib "") (part "3PIN TERMINALBOCK")))
    (comp (ref "U31") (value "LED") (libsource (lib "") (part "-LED")))
    (comp (ref "U32") (value "LED") (libsource (lib "") (part "-LED")))
    (comp (ref "U33")
      (value "NO")
      (fields (field (name "Manufacturer Part") "SRD-05VDC-SL-C") (field (name "Manufacturer") "松乐"))
      (libsource (lib "") (part "SRD-05VDC-SL-C"))
    )
    (comp (ref "U34")
      (value "2-PIN-MALE HEADER")
      (fields (field (name "Manufacturer Part") "87224-5") (field (name "Manufacturer") "TE Connectivity"))
      (libsource (lib "") (part "2-PIN-MALE HEADER"))
    )
    (comp (ref "U35")
      (value "6-pin male-male header")
      (fields (field (name "Manufacturer Part") "87224-5") (field (name "Manufacturer") "TE Connectivity"))
      (libsource (lib "") (part "6-pin male-male header"))
    )
    (comp (ref "U36") (value "1k potentiometer") (libsource (lib "") (part "Pot_blue")))
    (comp (ref "U37") (value "ARDUINO UNO GD32") (libsource (lib "") (part "ARDUINO UNO GD32")))
    (comp (ref "CN3") (value "PINHEADER-6PIN6") (libsource (lib "") (part "PINHEADER-6PIN6")))
    (comp (ref "U38") (value "NO") (libsource (lib "") (part "ESO_SPST_Momentary")))
    (comp (ref "U39") (value "NO") (libsource (lib "") (part "ESO_SPST_Momentary")))
    (comp (ref "U40") (value "NO") (libsource (lib "") (part "ESO_SPST_Momentary")))
    (comp (ref "U41") (value "NO") (libsource (lib "") (part "ESO_SPST_Momentary")))
    (comp (ref "U42") (value "NO") (libsource (lib "") (part "ESO_SPST_Momentary")))
    (comp (ref "U43") (value "NO") (libsource (lib "") (part "ESO_SPST_Momentary")))
    (comp (ref "U44") (value "NO") (libsource (lib "") (part "ESO_SPST_Momentary")))
    (comp (ref "U45") (value "NO") (libsource (lib "") (part "ESO_SPST_Momentary")))
    (comp (ref "U46") (value "NO") (libsource (lib "") (part "ESO_SPST_Momentary")))
    (comp (ref "U47") (value "ARDUINO UNO GD32") (libsource (lib "") (part "ARDUINO UNO GD32")))
    (comp (ref "LCD3") (value "LCD 16x2") (libsource (lib "") (part "LCD 16x2")))
    (comp (ref "U48") (value "1k potentiometer") (libsource (lib "") (part "Pot_blue")))
    (comp (ref "U49")
      (value "6-pin male-male header")
      (fields (field (name "Manufacturer Part") "87224-5") (field (name "Manufacturer") "TE Connectivity"))
      (libsource (lib "") (part "6-pin male-male header"))
    )
    (comp (ref "U50")
      (value "2-PIN-MALE HEADER")
      (fields (field (name "Manufacturer Part") "87224-5") (field (name "Manufacturer") "TE Connectivity"))
      (libsource (lib "") (part "2-PIN-MALE HEADER"))
    )
    (comp (ref "U51") (value "ARDUINO UNO GD32") (libsource (lib "") (part "ARDUINO UNO GD32")))
    (comp (ref "2.3K")
      (value "NO")
      (fields (field (name "Manufacturer") "Huaxing Mechanical-Elec."))
      (libsource (lib "") (part "1/4W-2.2KΩ±1%"))
    )
    (comp (ref "2R")
      (value "NO")
      (fields (field (name "Manufacturer") "Huaxing Mechanical-Elec."))
      (libsource (lib "") (part "1/4W-2.2KΩ±1%_1"))
    )
    (comp (ref "BUZZER3")
      (value "BUZZER")
      (fields (field (name "Manufacturer Part") "buzzer"))
      (libsource (lib "") (part "BUZZER"))
    )
    (comp (ref "C5")
      (value "100UF/16V")
      (fields (field (name "Manufacturer Part") "100uF/16V"))
      (libsource (lib "") (part "100UF/16V"))
    )
    (comp (ref "C6")
      (value "104")
      (fields
        (field (name "Manufacturer Part") "Suppression Capacitor222M/250V")
        (field (name "Manufacturer") "ReliaPro")
      )
      (libsource (lib "") (part "104nf"))
    )
    (comp (ref "LED2") (value "NO") (libsource (lib "") (part "-LED")))
    (comp (ref "P3")
      (value "HEADER PAD 3 PIN")
      (fields
        (field (name "Manufacturer Part") "Female headerHDR1X8-2.54")
        (field (name "Manufacturer") "BOOMELE")
      )
      (libsource (lib "") (part "HEADER PAD 3 PIN"))
    )
    (comp (ref "Q5")
      (value "BC557")
      (fields (field (name "Manufacturer") "CJ(江苏长电/长晶)"))
      (libsource (lib "") (part "BC557"))
    )
    (comp (ref "U52") (value "ARDUINO UNO GD32") (libsource (lib "") (part "ARDUINO UNO GD32")))
    (comp (ref "U53") (value "NO") (libsource (lib "") (part "EM-18")))
    (comp (ref "D3")
      (value "1N4007")
      (fields (field (name "Manufacturer") "ST(先科)"))
      (libsource (lib "") (part "1N4007"))
    )
    (comp (ref "Q6")
      (value "BC548B")
      (fields (field (name "Manufacturer Part") "BC548") (field (name "Manufacturer") "CJ(江苏长电/长晶)"))
      (libsource (lib "") (part "BC548B"))
    )
    (comp (ref "R7") (value "1000Ω") (libsource (lib "") (part "330Ω RESISTANCE_1")))
    (comp (ref "R8") (value "1000Ω") (libsource (lib "") (part "330Ω RESISTANCE_1")))
    (comp (ref "R9") (value "1000Ω") (libsource (lib "") (part "330Ω RESISTANCE")))
    (comp (ref "U54") (value "ARDUINO UNO GD32") (libsource (lib "") (part "ARDUINO UNO GD32")))
    (comp (ref "U55")
      (value "NO")
      (fields (field (name "Manufacturer Part") "SRD-05VDC-SL-C") (field (name "Manufacturer") "松乐"))
      (libsource (lib "") (part "SRD-05VDC-SL-C"))
    )
    (comp (ref "U56") (value "LED") (libsource (lib "") (part "-LED")))
    (comp (ref "U57") (value "LED") (libsource (lib "") (part "-LED")))
    (comp (ref "U58")
      (value "3 PIN MALE JAMPER")
      (fields (field (name "Manufacturer Part") "1x3 pin header") (field (name "Manufacturer") "NA"))
      (libsource (lib "") (part "3 PIN MALE JAMPER"))
    )
    (comp (ref "U59") (value "3PIN TERMINALBOCK") (libsource (lib "") (part "3PIN TERMINALBOCK")))
  )
  (nets
    (net (code "1") (name "C1") (class "Default")
      (node (ref "CN2") (pin "4") (pinfunction "C1_4") (pintype "input"))
      (node (ref "CN3") (pin "4") (pinfunction "C1_4") (pintype "input"))
      (node (ref "U19") (pin "1") (pinfunction "1_1") (pintype "unspecified"))
      (node (ref "U19") (pin "2") (pinfunction "2_2") (pintype "unspecified"))
      (node (ref "U22") (pin "1") (pinfunction "1_1") (pintype "unspecified"))
      (node (ref "U22") (pin "2") (pinfunction "2_2") (pintype "unspecified"))
      (node (ref "U27") (pin "1") (pinfunction "1_1") (pintype "unspecified"))
      (node (ref "U27") (pin "2") (pinfunction "2_2") (pintype "unspecified"))
      (node (ref "U37") (pin "9") (pinfunction "D8_9") (pintype "unspecified"))
      (node (ref "U38") (pin "1") (pinfunction "1_1") (pintype "unspecified"))
      (node (ref "U38") (pin "2") (pinfunction "2_2") (pintype "unspecified"))
      (node (ref "U43") (pin "1") (pinfunction "1_1") (pintype "unspecified"))
      (node (ref "U43") (pin "2") (pinfunction "2_2") (pintype "unspecified"))
      (node (ref "U46") (pin "1") (pinfunction "1_1") (pintype "unspecified"))
      (node (ref "U46") (pin "2") (pinfunction "2_2") (pintype "unspecified"))
      (node (ref "U47") (pin "9") (pinfunction "D8_9") (pintype "unspecified"))
    )
    (net (code "2") (name "C2") (class "Default")
      (node (ref "CN2") (pin "5") (pinfunction "C2_5") (pintype "input"))
      (node (ref "CN3") (pin "5") (pinfunction "C2_5") (pintype "input"))
      (node (ref "U20") (pin "1") (pinfunction "1_1") (pintype "unspecified"))
      (node (ref "U20") (pin "2") (pinfunction "2_2") (pintype "unspecified"))
      (node (ref "U23") (pin "1") (pinfunction "1_1") (pintype "unspecified"))
      (node (ref "U23") (pin "2") (pinfunction "2_2") (pintype "unspecified"))
      (node (ref "U26") (pin "1") (pinfunction "1_1") (pintype "unspecified"))
      (node (ref "U26") (pin "2") (pinfunction "2_2") (pintype "unspecified"))
      (node (ref "U37") (pin "10") (pinfunction "D9_10") (pintype "unspecified"))
      (node (ref "U39") (pin "1") (pinfunction "1_1") (pintype "unspecified"))
      (node (ref "U39") (pin "2") (pinfunction "2_2") (pintype "unspecified"))
      (node (ref "U42") (pin "1") (pinfunction "1_1") (pintype "unspecified"))
      (node (ref "U42") (pin "2") (pinfunction "2_2") (pintype "unspecified"))
      (node (ref "U45") (pin "1") (pinfunction "1_1") (pintype "unspecified"))
      (node (ref "U45") (pin "2") (pinfunction "2_2") (pintype "unspecified"))
      (node (ref "U47") (pin "10") (pinfunction "D9_10") (pintype "unspecified"))
    )
    (net (code "3") (name "C3") (class "Default")
      (node (ref "CN2") (pin "6") (pinfunction "C3_6") (pintype "input"))
      (node (ref "CN3") (pin "6") (pinfunction "C3_6") (pintype "input"))
      (node (ref "U21") (pin "1") (pinfunction "1_1") (pintype "unspecified"))
      (node (ref "U21") (pin "2") (pinfunction "2_2") (pintype "unspecified"))
      (node (ref "U24") (pin "1") (pinfunction "1_1") (pintype "unspecified"))
      (node (ref "U24") (pin "2") (pinfunction "2_2") (pintype "unspecified"))
      (node (ref "U25") (pin "1") (pinfunction "1_1") (pintype "unspecified"))
      (node (ref "U25") (pin "2") (pinfunction "2_2") (pintype "unspecified"))
      (node (ref "U37") (pin "11") (pinfunction "D10_11") (pintype "unspecified"))
      (node (ref "U40") (pin "1") (pinfunction "1_1") (pintype "unspecified"))
      (node (ref "U40") (pin "2") (pinfunction "2_2") (pintype "unspecified"))
      (node (ref "U41") (pin "1") (pinfunction "1_1") (pintype "unspecified"))
      (node (ref "U41") (pin "2") (pinfunction "2_2") (pintype "unspecified"))
      (node (ref "U44") (pin "1") (pinfunction "1_1") (pintype "unspecified"))
      (node (ref "U44") (pin "2") (pinfunction "2_2") (pintype "unspecified"))
      (node (ref "U47") (pin "11") (pinfunction "D10_11") (pintype "unspecified"))
    )
    (net (code "4") (name "COM") (class "Default")
      (node (ref "U11") (pin "3") (pinfunction "COM_3") (pintype "unspecified"))
      (node (ref "U14") (pin "2") (pinfunction "2_2") (pintype "unspecified"))
      (node (ref "U30") (pin "2") (pinfunction "2_2") (pintype "unspecified"))
      (node (ref "U33") (pin "3") (pinfunction "COM_3") (pintype "unspecified"))
      (node (ref "U37") (pin "25") (pinfunction "VIN_25") (pintype "passive"))
      (node (ref "U54") (pin "25") (pinfunction "VIN_25") (pintype "passive"))
      (node (ref "U55") (pin "3") (pinfunction "COM_3") (pintype "unspecified"))
      (node (ref "U59") (pin "2") (pinfunction "2_2") (pintype "unspecified"))
    )
    (net (code "5") (name "D4") (class "Default")
      (node (ref "LCD2") (pin "11") (pinfunction "DB4_11") (pintype "unspecified"))
      (node (ref "LCD3") (pin "11") (pinfunction "DB4_11") (pintype "unspecified"))
      (node (ref "U35") (pin "D4") (pinfunction "4_D4") (pintype "unspecified"))
      (node (ref "U37") (pin "21") (pinfunction "A3_21") (pintype "unspecified"))
      (node (ref "U49") (pin "D4") (pinfunction "4_D4") (pintype "unspecified"))
      (node (ref "U51") (pin "21") (pinfunction "A3_21") (pintype "unspecified"))
    )
    (net (code "6") (name "D5") (class "Default")
      (node (ref "LCD2") (pin "12") (pinfunction "DB5_12") (pintype "unspecified"))
      (node (ref "LCD3") (pin "12") (pinfunction "DB5_12") (pintype "unspecified"))
      (node (ref "U35") (pin "D5") (pinfunction "3_D5") (pintype "unspecified"))
      (node (ref "U37") (pin "22") (pinfunction "A2_22") (pintype "unspecified"))
      (node (ref "U49") (pin "D5") (pinfunction "3_D5") (pintype "unspecified"))
      (node (ref "U51") (pin "22") (pinfunction "A2_22") (pintype "unspecified"))
    )
    (net (code "7") (name "D6") (class "Default")
      (node (ref "LCD2") (pin "13") (pinfunction "DB6_13") (pintype "unspecified"))
      (node (ref "LCD3") (pin "13") (pinfunction "DB6_13") (pintype "unspecified"))
      (node (ref "U35") (pin "D6") (pinfunction "2_D6") (pintype "unspecified"))
      (node (ref "U37") (pin "23") (pinfunction "A1_23") (pintype "unspecified"))
      (node (ref "U49") (pin "D6") (pinfunction "2_D6") (pintype "unspecified"))
      (node (ref "U51") (pin "23") (pinfunction "A1_23") (pintype "unspecified"))
    )
    (net (code "8") (name "D7") (class "Default")
      (node (ref "LCD2") (pin "14") (pinfunction "DB7_14") (pintype "unspecified"))
      (node (ref "LCD3") (pin "14") (pinfunction "DB7_14") (pintype "unspecified"))
      (node (ref "U35") (pin "D7") (pinfunction "1_D7") (pintype "unspecified"))
      (node (ref "U37") (pin "24") (pinfunction "A0_24") (pintype "unspecified"))
      (node (ref "U49") (pin "D7") (pinfunction "1_D7") (pintype "unspecified"))
      (node (ref "U51") (pin "24") (pinfunction "A0_24") (pintype "unspecified"))
    )
    (net (code "9") (name "E") (class "Default")
      (node (ref "LCD2") (pin "6") (pinfunction "E_6") (pintype "unspecified"))
      (node (ref "LCD3") (pin "6") (pinfunction "E_6") (pintype "unspecified"))
      (node (ref "U35") (pin "E") (pinfunction "5_E") (pintype "unspecified"))
      (node (ref "U37") (pin "20") (pinfunction "A4_20") (pintype "unspecified"))
      (node (ref "U49") (pin "E") (pinfunction "5_E") (pintype "unspecified"))
      (node (ref "U51") (pin "20") (pinfunction "A4_20") (pintype "unspecified"))
    )
    (net (code "10") (name "GND") (class "Default")
      (node (ref "BUZZER1") (pin "1") (pinfunction "-_1") (pintype "unspecified"))
      (node (ref "BUZZER2") (pin "1") (pinfunction "-_1") (pintype "unspecified"))
      (node (ref "BUZZER3") (pin "1") (pinfunction "-_1") (pintype "unspecified"))
      (node (ref "C1") (pin "2") (pinfunction "2_2") (pintype "input"))
      (node (ref "C2") (pin "1") (pinfunction "1_1") (pintype "input"))
      (node (ref "C3") (pin "1") (pinfunction "1_1") (pintype "input"))
      (node (ref "C4") (pin "2") (pinfunction "2_2") (pintype "input"))
      (node (ref "C5") (pin "2") (pinfunction "2_2") (pintype "input"))
      (node (ref "C6") (pin "1") (pinfunction "1_1") (pintype "input"))
      (node (ref "LCD2") (pin "1") (pinfunction "Vss_1") (pintype "unspecified"))
      (node (ref "LCD2") (pin "16") (pinfunction "K_16") (pintype "unspecified"))
      (node (ref "LCD2") (pin "5") (pinfunction "RW_5") (pintype "unspecified"))
      (node (ref "LCD3") (pin "1") (pinfunction "Vss_1") (pintype "unspecified"))
      (node (ref "LCD3") (pin "16") (pinfunction "K_16") (pintype "unspecified"))
      (node (ref "LCD3") (pin "5") (pinfunction "RW_5") (pintype "unspecified"))
      (node (ref "LED") (pin "CATHODE") (pinfunction "CATHODE_CATHODE") (pintype "unspecified"))
      (node (ref "LED1") (pin "CATHODE") (pinfunction "CATHODE_CATHODE") (pintype "unspecified"))
      (node (ref "LED2") (pin "CATHODE") (pinfunction "CATHODE_CATHODE") (pintype "unspecified"))
      (node (ref "P1") (pin "2") (pinfunction "2_2") (pintype "input"))
      (node (ref "P2") (pin "2") (pinfunction "2_2") (pintype "input"))
      (node (ref "P3") (pin "2") (pinfunction "2_2") (pintype "input"))
      (node (ref "Q2") (pin "3") (pinfunction "E_3") (pintype "unspecified"))
      (node (ref "Q4") (pin "3") (pinfunction "E_3") (pintype "unspecified"))
      (node (ref "Q6") (pin "3") (pinfunction "E_3") (pintype "unspecified"))
      (node (ref "U10") (pin "3") (pinfunction "GND_3") (pintype "unspecified"))
      (node (ref "U13") (pin "CATHODE") (pinfunction "CATHODE_CATHODE") (pintype "unspecified"))
      (node (ref "U15") (pin "2") (pinfunction "2_2") (pintype "unspecified"))
      (node (ref "U28") (pin "3") (pinfunction "GND_3") (pintype "unspecified"))
      (node (ref "U29") (pin "2") (pinfunction "2_2") (pintype "unspecified"))
      (node (ref "U31") (pin "CATHODE") (pinfunction "CATHODE_CATHODE") (pintype "unspecified"))
      (node (ref "U34") (pin "GND") (pinfunction "2_GND") (pintype "unspecified"))
      (node (ref "U36") (pin "1") (pinfunction "1_1") (pintype "input"))
      (node (ref "U37") (pin "26") (pinfunction "GND1_26") (pintype "passive"))
      (node (ref "U48") (pin "1") (pinfunction "1_1") (pintype "input"))
      (node (ref "U50") (pin "GND") (pinfunction "2_GND") (pintype "unspecified"))
      (node (ref "U51") (pin "26") (pinfunction "GND1_26") (pintype "passive"))
      (node (ref "U52") (pin "26") (pinfunction "GND1_26") (pintype "passive"))
      (node (ref "U53") (pin "3") (pinfunction "GND_3") (pintype "unspecified"))
      (node (ref "U54") (pin "26") (pinfunction "GND1_26") (pintype "passive"))
      (node (ref "U57") (pin "CATHODE") (pinfunction "CATHODE_CATHODE") (pintype "unspecified"))
      (node (ref "U58") (pin "2") (pinfunction "2_2") (pintype "unspecified"))
    )
    (net (code "11") (name "IN") (class "Default")
      (node (ref "R3") (pin "2") (pinfunction "2_2") (pintype "unspecified"))
      (node (ref "R4") (pin "2") (pinfunction "2_2") (pintype "unspecified"))
      (node (ref "R9") (pin "2") (pinfunction "2_2") (pintype "unspecified"))
      (node (ref "U15") (pin "3") (pinfunction "3_3") (pintype "unspecified"))
      (node (ref "U29") (pin "3") (pinfunction "3_3") (pintype "unspecified"))
      (node (ref "U37") (pin "3") (pinfunction "D2_3") (pintype "unspecified"))
      (node (ref "U54") (pin "3") (pinfunction "D2_3") (pintype "unspecified"))
      (node (ref "U58") (pin "3") (pinfunction "3_3") (pintype "unspecified"))
    )
    (net (code "12") (name "NC") (class "Default")
      (node (ref "U11") (pin "4") (pinfunction "NC_4") (pintype "unspecified"))
      (node (ref "U14") (pin "1") (pinfunction "1_1") (pintype "unspecified"))
      (node (ref "U30") (pin "1") (pinfunction "1_1") (pintype "unspecified"))
      (node (ref "U33") (pin "4") (pinfunction "NC_4") (pintype "unspecified"))
      (node (ref "U55") (pin "4") (pinfunction "NC_4") (pintype "unspecified"))
      (node (ref "U59") (pin "1") (pinfunction "1_1") (pintype "unspecified"))
    )
    (net (code "13") (name "NO") (class "Default")
      (node (ref "U14") (pin "3") (pinfunction "3_3") (pintype "unspecified"))
      (node (ref "U30") (pin "3") (pinfunction "3_3") (pintype "unspecified"))
      (node (ref "U59") (pin "3") (pinfunction "3_3") (pintype "unspecified"))
    )
    (net (code "14") (name "Net-(1R-Pad2)") (class "Default")
      (node (ref "1R") (pin "2") (pinfunction "2_2") (pintype "unspecified"))
      (node (ref "LED1") (pin "ANODE") (pinfunction "ANODE_ANODE") (pintype "unspecified"))
    )
    (net (code "15") (name "Net-(2R-Pad2)") (class "Default")
      (node (ref "2R") (pin "2") (pinfunction "2_2") (pintype "unspecified"))
      (node (ref "LED2") (pin "ANODE") (pinfunction "ANODE_ANODE") (pintype "unspecified"))
    )
    (net (code "16") (name "Net-(470R-Pad2)") (class "Default")
      (node (ref "470R") (pin "2") (pinfunction "2_2") (pintype "unspecified"))
      (node (ref "LED") (pin "ANODE") (pinfunction "ANODE_ANODE") (pintype "unspecified"))
    )
    (net (code "17") (name "Net-(BUZZER1-+)") (class "Default")
      (node (ref "470R") (pin "1") (pinfunction "1_1") (pintype "unspecified"))
      (node (ref "BUZZER1") (pin "2") (pinfunction "+_2") (pintype "unspecified"))
      (node (ref "Q1") (pin "1") (pinfunction "C_1") (pintype "unspecified"))
    )
    (net (code "18") (name "Net-(BUZZER2-+)") (class "Default")
      (node (ref "1R") (pin "1") (pinfunction "1_1") (pintype "unspecified"))
      (node (ref "BUZZER2") (pin "2") (pinfunction "+_2") (pintype "unspecified"))
      (node (ref "Q3") (pin "1") (pinfunction "C_1") (pintype "unspecified"))
    )
    (net (code "19") (name "Net-(BUZZER3-+)") (class "Default")
      (node (ref "2R") (pin "1") (pinfunction "1_1") (pintype "unspecified"))
      (node (ref "BUZZER3") (pin "2") (pinfunction "+_2") (pintype "unspecified"))
      (node (ref "Q5") (pin "1") (pinfunction "C_1") (pintype "unspecified"))
    )
    (net (code "20") (name "Net-(CN1-C1)") (class "Default")
      (node (ref "CN1") (pin "4") (pinfunction "C1_4") (pintype "input"))
      (node (ref "U1") (pin "1") (pinfunction "1_1") (pintype "unspecified"))
      (node (ref "U1") (pin "2") (pinfunction "2_2") (pintype "unspecified"))
      (node (ref "U6") (pin "1") (pinfunction "1_1") (pintype "unspecified"))
      (node (ref "U6") (pin "2") (pinfunction "2_2") (pintype "unspecified"))
      (node (ref "U9") (pin "1") (pinfunction "1_1") (pintype "unspecified"))
      (node (ref "U9") (pin "2") (pinfunction "2_2") (pintype "unspecified"))
    )
    (net (code "21") (name "Net-(CN1-C2)") (class "Default")
      (node (ref "CN1") (pin "5") (pinfunction "C2_5") (pintype "input"))
      (node (ref "U2") (pin "1") (pinfunction "1_1") (pintype "unspecified"))
      (node (ref "U2") (pin "2") (pinfunction "2_2") (pintype "unspecified"))
      (node (ref "U5") (pin "1") (pinfunction "1_1") (pintype "unspecified"))
      (node (ref "U5") (pin "2") (pinfunction "2_2") (pintype "unspecified"))
      (node (ref "U8") (pin "1") (pinfunction "1_1") (pintype "unspecified"))
      (node (ref "U8") (pin "2") (pinfunction "2_2") (pintype "unspecified"))
    )
    (net (code "22") (name "Net-(CN1-C3)") (class "Default")
      (node (ref "CN1") (pin "6") (pinfunction "C3_6") (pintype "input"))
      (node (ref "U3") (pin "1") (pinfunction "1_1") (pintype "unspecified"))
      (node (ref "U3") (pin "2") (pinfunction "2_2") (pintype "unspecified"))
      (node (ref "U4") (pin "1") (pinfunction "1_1") (pintype "unspecified"))
      (node (ref "U4") (pin "2") (pinfunction "2_2") (pintype "unspecified"))
      (node (ref "U7") (pin "1") (pinfunction "1_1") (pintype "unspecified"))
      (node (ref "U7") (pin "2") (pinfunction "2_2") (pintype "unspecified"))
    )
    (net (code "23") (name "Net-(CN1-R1)") (class "Default")
      (node (ref "CN1") (pin "1") (pinfunction "R1_1") (pintype "input"))
      (node (ref "U1") (pin "3") (pinfunction "3_3") (pintype "unspecified"))
      (node (ref "U1") (pin "4") (pinfunction "4_4") (pintype "unspecified"))
      (node (ref "U2") (pin "3") (pinfunction "3_3") (pintype "unspecified"))
      (node (ref "U2") (pin "4") (pinfunction "4_4") (pintype "unspecified"))
      (node (ref "U3") (pin "3") (pinfunction "3_3") (pintype "unspecified"))
      (node (ref "U3") (pin "4") (pinfunction "4_4") (pintype "unspecified"))
    )
    (net (code "24") (name "Net-(CN1-R2)") (class "Default")
      (node (ref "CN1") (pin "2") (pinfunction "R2_2") (pintype "input"))
      (node (ref "U4") (pin "3") (pinfunction "3_3") (pintype "unspecified"))
      (node (ref "U4") (pin "4") (pinfunction "4_4") (pintype "unspecified"))
      (node (ref "U5") (pin "3") (pinfunction "3_3") (pintype "unspecified"))
      (node (ref "U5") (pin "4") (pinfunction "4_4") (pintype "unspecified"))
      (node (ref "U6") (pin "3") (pinfunction "3_3") (pintype "unspecified"))
      (node (ref "U6") (pin "4") (pinfunction "4_4") (pintype "unspecified"))
    )
    (net (code "25") (name "Net-(CN1-R3)") (class "Default")
      (node (ref "CN1") (pin "3") (pinfunction "R3_3") (pintype "input"))
      (node (ref "U7") (pin "3") (pinfunction "3_3") (pintype "unspecified"))
      (node (ref "U7") (pin "4") (pinfunction "4_4") (pintype "unspecified"))
      (node (ref "U8") (pin "3") (pinfunction "3_3") (pintype "unspecified"))
      (node (ref "U8") (pin "4") (pinfunction "4_4") (pintype "unspecified"))
      (node (ref "U9") (pin "3") (pinfunction "3_3") (pintype "unspecified"))
      (node (ref "U9") (pin "4") (pinfunction "4_4") (pintype "unspecified"))
    )
    (net (code "26") (name "Net-(D1-A)") (class "Default")
      (node (ref "D1") (pin "2") (pinfunction "A_2") (pintype "unspecified"))
      (node (ref "Q2") (pin "1") (pinfunction "C_1") (pintype "unspecified"))
      (node (ref "U11") (pin "1") (pinfunction "OT_1") (pintype "unspecified"))
      (node (ref "U12") (pin "CATHODE") (pinfunction "CATHODE_CATHODE") (pintype "unspecified"))
    )
    (net (code "27") (name "Net-(D2-A)") (class "Default")
      (node (ref "D2") (pin "2") (pinfunction "A_2") (pintype "unspecified"))
      (node (ref "Q4") (pin "1") (pinfunction "C_1") (pintype "unspecified"))
      (node (ref "U32") (pin "CATHODE") (pinfunction "CATHODE_CATHODE") (pintype "unspecified"))
      (node (ref "U33") (pin "1") (pinfunction "OT_1") (pintype "unspecified"))
    )
    (net (code "28") (name "Net-(D3-A)") (class "Default")
      (node (ref "D3") (pin "2") (pinfunction "A_2") (pintype "unspecified"))
      (node (ref "Q6") (pin "1") (pinfunction "C_1") (pintype "unspecified"))
      (node (ref "U55") (pin "1") (pinfunction "OT_1") (pintype "unspecified"))
      (node (ref "U56") (pin "CATHODE") (pinfunction "CATHODE_CATHODE") (pintype "unspecified"))
    )
    (net (code "29") (name "Net-(LCD1-A)") (class "Default")
      (node (ref "LCD1") (pin "15") (pinfunction "A_15") (pintype "unspecified"))
      (node (ref "LCD1") (pin "2") (pinfunction "Vdd_2") (pintype "unspecified"))
      (node (ref "U17") (pin "3") (pinfunction "2_3") (pintype "input"))
      (node (ref "U18") (pin "1") (pinfunction "1_1") (pintype "unspecified"))
    )
    (net (code "30") (name "Net-(LCD1-DB4)") (class "Default")
      (node (ref "LCD1") (pin "11") (pinfunction "DB4_11") (pintype "unspecified"))
      (node (ref "U16") (pin "4") (pinfunction "4_4") (pintype "unspecified"))
    )
    (net (code "31") (name "Net-(LCD1-DB5)") (class "Default")
      (node (ref "LCD1") (pin "12") (pinfunction "DB5_12") (pintype "unspecified"))
      (node (ref "U16") (pin "3") (pinfunction "3_3") (pintype "unspecified"))
    )
    (net (code "32") (name "Net-(LCD1-DB6)") (class "Default")
      (node (ref "LCD1") (pin "13") (pinfunction "DB6_13") (pintype "unspecified"))
      (node (ref "U16") (pin "2") (pinfunction "2_2") (pintype "unspecified"))
    )
    (net (code "33") (name "Net-(LCD1-DB7)") (class "Default")
      (node (ref "LCD1") (pin "14") (pinfunction "DB7_14") (pintype "unspecified"))
      (node (ref "U16") (pin "1") (pinfunction "1_1") (pintype "unspecified"))
    )
    (net (code "34") (name "Net-(LCD1-E)") (class "Default")
      (node (ref "LCD1") (pin "6") (pinfunction "E_6") (pintype "unspecified"))
      (node (ref "U16") (pin "5") (pinfunction "5_5") (pintype "unspecified"))
    )
    (net (code "35") (name "Net-(LCD1-K)") (class "Default")
      (node (ref "LCD1") (pin "1") (pinfunction "Vss_1") (pintype "unspecified"))
      (node (ref "LCD1") (pin "16") (pinfunction "K_16") (pintype "unspecified"))
      (node (ref "LCD1") (pin "5") (pinfunction "RW_5") (pintype "unspecified"))
      (node (ref "U17") (pin "1") (pinfunction "1_1") (pintype "input"))
      (node (ref "U18") (pin "2") (pinfunction "2_2") (pintype "unspecified"))
    )
    (net (code "36") (name "Net-(LCD1-RS)") (class "Default")
      (node (ref "LCD1") (pin "4") (pinfunction "RS_4") (pintype "unspecified"))
      (node (ref "U16") (pin "6") (pinfunction "6_6") (pintype "unspecified"))
    )
    (net (code "37") (name "Net-(LCD1-V0)") (class "Default")
      (node (ref "LCD1") (pin "3") (pinfunction "V0_3") (pintype "unspecified"))
      (node (ref "U17") (pin "2") (pinfunction "3_2") (pintype "input"))
    )
    (net (code "38") (name "Net-(LCD2-V0)") (class "Default")
      (node (ref "LCD2") (pin "3") (pinfunction "V0_3") (pintype "unspecified"))
      (node (ref "U36") (pin "2") (pinfunction "3_2") (pintype "input"))
    )
    (net (code "39") (name "Net-(LCD3-V0)") (class "Default")
      (node (ref "LCD3") (pin "3") (pinfunction "V0_3") (pintype "unspecified"))
      (node (ref "U48") (pin "2") (pinfunction "3_2") (pintype "input"))
    )
    (net (code "40") (name "Net-(Q1-B)") (class "Default")
      (node (ref "2.2K") (pin "2") (pinfunction "2_2") (pintype "unspecified"))
      (node (ref "Q1") (pin "2") (pinfunction "B_2") (pintype "unspecified"))
    )
    (net (code "41") (name "Net-(Q2-B)") (class "Default")
      (node (ref "Q2") (pin "2") (pinfunction "B_2") (pintype "unspecified"))
      (node (ref "R3") (pin "1") (pinfunction "1_1") (pintype "unspecified"))
    )
    (net (code "42") (name "Net-(Q3-B)") (class "Default")
      (node (ref "2.1K") (pin "2") (pinfunction "2_2") (pintype "unspecified"))
      (node (ref "Q3") (pin "2") (pinfunction "B_2") (pintype "unspecified"))
    )
    (net (code "43") (name "Net-(Q4-B)") (class "Default")
      (node (ref "Q4") (pin "2") (pinfunction "B_2") (pintype "unspecified"))
      (node (ref "R4") (pin "1") (pinfunction "1_1") (pintype "unspecified"))
    )
    (net (code "44") (name "Net-(Q5-B)") (class "Default")
      (node (ref "2.3K") (pin "2") (pinfunction "2_2") (pintype "unspecified"))
      (node (ref "Q5") (pin "2") (pinfunction "B_2") (pintype "unspecified"))
    )
    (net (code "45") (name "Net-(Q6-B)") (class "Default")
      (node (ref "Q6") (pin "2") (pinfunction "B_2") (pintype "unspecified"))
      (node (ref "R9") (pin "1") (pinfunction "1_1") (pintype "unspecified"))
    )
    (net (code "46") (name "Net-(R1-Pad1)") (class "Default")
      (node (ref "R1") (pin "1") (pinfunction "1_1") (pintype "unspecified"))
      (node (ref "U12") (pin "ANODE") (pinfunction "ANODE_ANODE") (pintype "unspecified"))
    )
    (net (code "47") (name "Net-(R2-Pad1)") (class "Default")
      (node (ref "R2") (pin "1") (pinfunction "1_1") (pintype "unspecified"))
      (node (ref "U13") (pin "ANODE") (pinfunction "ANODE_ANODE") (pintype "unspecified"))
    )
    (net (code "48") (name "Net-(R5-Pad1)") (class "Default")
      (node (ref "R5") (pin "1") (pinfunction "1_1") (pintype "unspecified"))
      (node (ref "U31") (pin "ANODE") (pinfunction "ANODE_ANODE") (pintype "unspecified"))
    )
    (net (code "49") (name "Net-(R6-Pad1)") (class "Default")
      (node (ref "R6") (pin "1") (pinfunction "1_1") (pintype "unspecified"))
      (node (ref "U32") (pin "ANODE") (pinfunction "ANODE_ANODE") (pintype "unspecified"))
    )
    (net (code "50") (name "Net-(R7-Pad1)") (class "Default")
      (node (ref "R7") (pin "1") (pinfunction "1_1") (pintype "unspecified"))
      (node (ref "U56") (pin "ANODE") (pinfunction "ANODE_ANODE") (pintype "unspecified"))
    )
    (net (code "51") (name "Net-(R8-Pad1)") (class "Default")
      (node (ref "R8") (pin "1") (pinfunction "1_1") (pintype "unspecified"))
      (node (ref "U57") (pin "ANODE") (pinfunction "ANODE_ANODE") (pintype "unspecified"))
    )
    (net (code "52") (name "Net-(U10-LED)") (class "Default")
      (node (ref "2.2K") (pin "1") (pinfunction "1_1") (pintype "unspecified"))
      (node (ref "U10") (pin "4") (pinfunction "LED_4") (pintype "unspecified"))
    )
    (net (code "53") (name "Net-(U28-LED)") (class "Default")
      (node (ref "2.1K") (pin "1") (pinfunction "1_1") (pintype "unspecified"))
      (node (ref "U28") (pin "4") (pinfunction "LED_4") (pintype "unspecified"))
    )
    (net (code "54") (name "Net-(U53-LED)") (class "Default")
      (node (ref "2.3K") (pin "1") (pinfunction "1_1") (pintype "unspecified"))
      (node (ref "U53") (pin "4") (pinfunction "LED_4") (pintype "unspecified"))
    )
    (net (code "55") (name "OUT") (class "Default")
      (node (ref "P1") (pin "3") (pinfunction "3_3") (pintype "input"))
      (node (ref "P2") (pin "3") (pinfunction "3_3") (pintype "input"))
      (node (ref "P3") (pin "3") (pinfunction "3_3") (pintype "input"))
      (node (ref "U10") (pin "8") (pinfunction "TX_8") (pintype "unspecified"))
      (node (ref "U28") (pin "8") (pinfunction "TX_8") (pintype "unspecified"))
      (node (ref "U37") (pin "1") (pinfunction "D0_1") (pintype "unspecified"))
      (node (ref "U52") (pin "1") (pinfunction "D0_1") (pintype "unspecified"))
      (node (ref "U53") (pin "8") (pinfunction "TX_8") (pintype "unspecified"))
    )
    (net (code "56") (name "R1") (class "Default")
      (node (ref "CN2") (pin "1") (pinfunction "R1_1") (pintype "input"))
      (node (ref "CN3") (pin "1") (pinfunction "R1_1") (pintype "input"))
      (node (ref "U25") (pin "3") (pinfunction "3_3") (pintype "unspecified"))
      (node (ref "U25") (pin "4") (pinfunction "4_4") (pintype "unspecified"))
      (node (ref "U26") (pin "3") (pinfunction "3_3") (pintype "unspecified"))
      (node (ref "U26") (pin "4") (pinfunction "4_4") (pintype "unspecified"))
      (node (ref "U27") (pin "3") (pinfunction "3_3") (pintype "unspecified"))
      (node (ref "U27") (pin "4") (pinfunction "4_4") (pintype "unspecified"))
      (node (ref "U37") (pin "6") (pinfunction "D5_6") (pintype "unspecified"))
      (node (ref "U38") (pin "3") (pinfunction "3_3") (pintype "unspecified"))
      (node (ref "U38") (pin "4") (pinfunction "4_4") (pintype "unspecified"))
      (node (ref "U39") (pin "3") (pinfunction "3_3") (pintype "unspecified"))
      (node (ref "U39") (pin "4") (pinfunction "4_4") (pintype "unspecified"))
      (node (ref "U40") (pin "3") (pinfunction "3_3") (pintype "unspecified"))
      (node (ref "U40") (pin "4") (pinfunction "4_4") (pintype "unspecified"))
      (node (ref "U47") (pin "6") (pinfunction "D5_6") (pintype "unspecified"))
    )
    (net (code "57") (name "R2") (class "Default")
      (node (ref "CN2") (pin "2") (pinfunction "R2_2") (pintype "input"))
      (node (ref "CN3") (pin "2") (pinfunction "R2_2") (pintype "input"))
      (node (ref "U22") (pin "3") (pinfunction "3_3") (pintype "unspecified"))
      (node (ref "U22") (pin "4") (pinfunction "4_4") (pintype "unspecified"))
      (node (ref "U23") (pin "3") (pinfunction "3_3") (pintype "unspecified"))
      (node (ref "U23") (pin "4") (pinfunction "4_4") (pintype "unspecified"))
      (node (ref "U24") (pin "3") (pinfunction "3_3") (pintype "unspecified"))
      (node (ref "U24") (pin "4") (pinfunction "4_4") (pintype "unspecified"))
      (node (ref "U37") (pin "7") (pinfunction "D6_7") (pintype "unspecified"))
      (node (ref "U41") (pin "3") (pinfunction "3_3") (pintype "unspecified"))
      (node (ref "U41") (pin "4") (pinfunction "4_4") (pintype "unspecified"))
      (node (ref "U42") (pin "3") (pinfunction "3_3") (pintype "unspecified"))
      (node (ref "U42") (pin "4") (pinfunction "4_4") (pintype "unspecified"))
      (node (ref "U43") (pin "3") (pinfunction "3_3") (pintype "unspecified"))
      (node (ref "U43") (pin "4") (pinfunction "4_4") (pintype "unspecified"))
      (node (ref "U47") (pin "7") (pinfunction "D6_7") (pintype "unspecified"))
    )
    (net (code "58") (name "R3") (class "Default")
      (node (ref "CN2") (pin "3") (pinfunction "R3_3") (pintype "input"))
      (node (ref "CN3") (pin "3") (pinfunction "R3_3") (pintype "input"))
      (node (ref "U19") (pin "3") (pinfunction "3_3") (pintype "unspecified"))
      (node (ref "U19") (pin "4") (pinfunction "4_4") (pintype "unspecified"))
      (node (ref "U20") (pin "3") (pinfunction "3_3") (pintype "unspecified"))
      (node (ref "U20") (pin "4") (pinfunction "4_4") (pintype "unspecified"))
      (node (ref "U21") (pin "3") (pinfunction "3_3") (pintype "unspecified"))
      (node (ref "U21") (pin "4") (pinfunction "4_4") (pintype "unspecified"))
      (node (ref "U37") (pin "8") (pinfunction "D7_8") (pintype "unspecified"))
      (node (ref "U44") (pin "3") (pinfunction "3_3") (pintype "unspecified"))
      (node (ref "U44") (pin "4") (pinfunction "4_4") (pintype "unspecified"))
      (node (ref "U45") (pin "3") (pinfunction "3_3") (pintype "unspecified"))
      (node (ref "U45") (pin "4") (pinfunction "4_4") (pintype "unspecified"))
      (node (ref "U46") (pin "3") (pinfunction "3_3") (pintype "unspecified"))
      (node (ref "U46") (pin "4") (pinfunction "4_4") (pintype "unspecified"))
      (node (ref "U47") (pin "8") (pinfunction "D7_8") (pintype "unspecified"))
    )
    (net (code "59") (name "RS") (class "Default")
      (node (ref "LCD2") (pin "4") (pinfunction "RS_4") (pintype "unspecified"))
      (node (ref "LCD3") (pin "4") (pinfunction "RS_4") (pintype "unspecified"))
      (node (ref "U35") (pin "RS") (pinfunction "6_RS") (pintype "unspecified"))
      (node (ref "U37") (pin "19") (pinfunction "A5_19") (pintype "unspecified"))
      (node (ref "U49") (pin "RS") (pinfunction "6_RS") (pintype "unspecified"))
      (node (ref "U51") (pin "19") (pinfunction "A5_19") (pintype "unspecified"))
    )
    (net (code "60") (name "VCC") (class "Default")
      (node (ref "C1") (pin "1") (pinfunction "1_1") (pintype "input"))
      (node (ref "C2") (pin "2") (pinfunction "2_2") (pintype "input"))
      (node (ref "C3") (pin "2") (pinfunction "2_2") (pintype "input"))
      (node (ref "C4") (pin "1") (pinfunction "1_1") (pintype "input"))
      (node (ref "C5") (pin "1") (pinfunction "1_1") (pintype "input"))
      (node (ref "C6") (pin "2") (pinfunction "2_2") (pintype "input"))
      (node (ref "D1") (pin "1") (pinfunction "K_1") (pintype "unspecified"))
      (node (ref "D2") (pin "1") (pinfunction "K_1") (pintype "unspecified"))
      (node (ref "D3") (pin "1") (pinfunction "K_1") (pintype "unspecified"))
      (node (ref "LCD2") (pin "15") (pinfunction "A_15") (pintype "unspecified"))
      (node (ref "LCD2") (pin "2") (pinfunction "Vdd_2") (pintype "unspecified"))
      (node (ref "LCD3") (pin "15") (pinfunction "A_15") (pintype "unspecified"))
      (node (ref "LCD3") (pin "2") (pinfunction "Vdd_2") (pintype "unspecified"))
      (node (ref "P1") (pin "1") (pinfunction "1_1") (pintype "input"))
      (node (ref "P2") (pin "1") (pinfunction "1_1") (pintype "input"))
      (node (ref "P3") (pin "1") (pinfunction "1_1") (pintype "input"))
      (node (ref "Q1") (pin "3") (pinfunction "E_3") (pintype "unspecified"))
      (node (ref "Q3") (pin "3") (pinfunction "E_3") (pintype "unspecified"))
      (node (ref "Q5") (pin "3") (pinfunction "E_3") (pintype "unspecified"))
      (node (ref "R1") (pin "2") (pinfunction "2_2") (pintype "unspecified"))
      (node (ref "R2") (pin "2") (pinfunction "2_2") (pintype "unspecified"))
      (node (ref "R5") (pin "2") (pinfunction "2_2") (pintype "unspecified"))
      (node (ref "R6") (pin "2") (pinfunction "2_2") (pintype "unspecified"))
      (node (ref "R7") (pin "2") (pinfunction "2_2") (pintype "unspecified"))
      (node (ref "R8") (pin "2") (pinfunction "2_2") (pintype "unspecified"))
      (node (ref "U10") (pin "1") (pinfunction "VCC_1") (pintype "unspecified"))
      (node (ref "U10") (pin "7") (pinfunction "SEL_7") (pintype "unspecified"))
      (node (ref "U11") (pin "2") (pinfunction "IN_2") (pintype "unspecified"))
      (node (ref "U15") (pin "1") (pinfunction "1_1") (pintype "unspecified"))
      (node (ref "U28") (pin "1") (pinfunction "VCC_1") (pintype "unspecified"))
      (node (ref "U28") (pin "7") (pinfunction "SEL_7") (pintype "unspecified"))
      (node (ref "U29") (pin "1") (pinfunction "1_1") (pintype "unspecified"))
      (node (ref "U33") (pin "2") (pinfunction "IN_2") (pintype "unspecified"))
      (node (ref "U34") (pin "VCC") (pinfunction "1_VCC") (pintype "unspecified"))
      (node (ref "U36") (pin "3") (pinfunction "2_3") (pintype "input"))
      (node (ref "U37") (pin "28") (pinfunction "5V_28") (pintype "passive"))
      (node (ref "U48") (pin "3") (pinfunction "2_3") (pintype "input"))
      (node (ref "U50") (pin "VCC") (pinfunction "1_VCC") (pintype "unspecified"))
      (node (ref "U51") (pin "28") (pinfunction "5V_28") (pintype "passive"))
      (node (ref "U52") (pin "28") (pinfunction "5V_28") (pintype "passive"))
      (node (ref "U53") (pin "1") (pinfunction "VCC_1") (pintype "unspecified"))
      (node (ref "U53") (pin "7") (pinfunction "SEL_7") (pintype "unspecified"))
      (node (ref "U54") (pin "28") (pinfunction "5V_28") (pintype "passive"))
      (node (ref "U55") (pin "2") (pinfunction "IN_2") (pintype "unspecified"))
      (node (ref "U58") (pin "1") (pinfunction "1_1") (pintype "unspecified"))
    )
    (net (code "61") (name "unconnected-(+-K-Pad2)") (class "Default")
      (node (ref "+") (pin "2") (pinfunction "K_2") (pintype "bidirectional"))
    )
    (net (code "62") (name "unconnected-(--K-Pad2)") (class "Default")
      (node (ref "-") (pin "2") (pinfunction "K_2") (pintype "bidirectional"))
    )
    (net (code "63") (name "unconnected-(LCD1-DB0-Pad7)") (class "Default")
      (node (ref "LCD1") (pin "7") (pinfunction "DB0_7") (pintype "unspecified"))
    )
    (net (code "64") (name "unconnected-(LCD1-DB1-Pad8)") (class "Default")
      (node (ref "LCD1") (pin "8") (pinfunction "DB1_8") (pintype "unspecified"))
    )
    (net (code "65") (name "unconnected-(LCD1-DB2-Pad9)") (class "Default")
      (node (ref "LCD1") (pin "9") (pinfunction "DB2_9") (pintype "unspecified"))
    )
    (net (code "66") (name "unconnected-(LCD1-DB3-Pad10)") (class "Default")
      (node (ref "LCD1") (pin "10") (pinfunction "DB3_10") (pintype "unspecified"))
    )
    (net (code "67") (name "unconnected-(LCD2-DB0-Pad7)") (class "Default")
      (node (ref "LCD2") (pin "7") (pinfunction "DB0_7") (pintype "unspecified"))
    )
    (net (code "68") (name "unconnected-(LCD2-DB1-Pad8)") (class "Default")
      (node (ref "LCD2") (pin "8") (pinfunction "DB1_8") (pintype "unspecified"))
    )
    (net (code "69") (name "unconnected-(LCD2-DB2-Pad9)") (class "Default")
      (node (ref "LCD2") (pin "9") (pinfunction "DB2_9") (pintype "unspecified"))
    )
    (net (code "70") (name "unconnected-(LCD2-DB3-Pad10)") (class "Default")
      (node (ref "LCD2") (pin "10") (pinfunction "DB3_10") (pintype "unspecified"))
    )
    (net (code "71") (name "unconnected-(LCD3-DB0-Pad7)") (class "Default")
      (node (ref "LCD3") (pin "7") (pinfunction "DB0_7") (pintype "unspecified"))
    )
    (net (code "72") (name "unconnected-(LCD3-DB1-Pad8)") (class "Default")
      (node (ref "LCD3") (pin "8") (pinfunction "DB1_8") (pintype "unspecified"))
    )
    (net (code "73") (name "unconnected-(LCD3-DB2-Pad9)") (class "Default")
      (node (ref "LCD3") (pin "9") (pinfunction "DB2_9") (pintype "unspecified"))
    )
    (net (code "74") (name "unconnected-(LCD3-DB3-Pad10)") (class "Default")
      (node (ref "LCD3") (pin "10") (pinfunction "DB3_10") (pintype "unspecified"))
    )
    (net (code "75") (name "unconnected-(U10-D1-Pad9)") (class "Default")
      (node (ref "U10") (pin "9") (pinfunction "D1_9") (pintype "unspecified"))
    )
    (net (code "76") (name "unconnected-(U10-D2-Pad10)") (class "Default")
      (node (ref "U10") (pin "10") (pinfunction "D2_10") (pintype "unspecified"))
    )
    (net (code "77") (name "unconnected-(U10-NC-Pad2)") (class "Default")
      (node (ref "U10") (pin "2") (pinfunction "NC_2") (pintype "unspecified"))
    )
    (net (code "78") (name "unconnected-(U10-NC-Pad5)") (class "Default")
      (node (ref "U10") (pin "5") (pinfunction "NC_5") (pintype "unspecified"))
    )
    (net (code "79") (name "unconnected-(U10-NC-Pad6)") (class "Default")
      (node (ref "U10") (pin "6") (pinfunction "NC_6") (pintype "unspecified"))
    )
    (net (code "80") (name "unconnected-(U11-NO-Pad5)") (class "Default")
      (node (ref "U11") (pin "5") (pinfunction "NO_5") (pintype "unspecified"))
    )
    (net (code "81") (name "unconnected-(U28-D1-Pad9)") (class "Default")
      (node (ref "U28") (pin "9") (pinfunction "D1_9") (pintype "unspecified"))
    )
    (net (code "82") (name "unconnected-(U28-D2-Pad10)") (class "Default")
      (node (ref "U28") (pin "10") (pinfunction "D2_10") (pintype "unspecified"))
    )
    (net (code "83") (name "unconnected-(U28-NC-Pad2)") (class "Default")
      (node (ref "U28") (pin "2") (pinfunction "NC_2") (pintype "unspecified"))
    )
    (net (code "84") (name "unconnected-(U28-NC-Pad5)") (class "Default")
      (node (ref "U28") (pin "5") (pinfunction "NC_5") (pintype "unspecified"))
    )
    (net (code "85") (name "unconnected-(U28-NC-Pad6)") (class "Default")
      (node (ref "U28") (pin "6") (pinfunction "NC_6") (pintype "unspecified"))
    )
    (net (code "86") (name "unconnected-(U33-NO-Pad5)") (class "Default")
      (node (ref "U33") (pin "5") (pinfunction "NO_5") (pintype "unspecified"))
    )
    (net (code "87") (name "unconnected-(U37-3V-Pad29)") (class "Default")
      (node (ref "U37") (pin "29") (pinfunction "3V_29") (pintype "passive"))
    )
    (net (code "88") (name "unconnected-(U37-AREF-Pad16)") (class "Default")
      (node (ref "U37") (pin "16") (pinfunction "AREF_16") (pintype "unspecified"))
    )
    (net (code "89") (name "unconnected-(U37-D1-Pad2)") (class "Default")
      (node (ref "U37") (pin "2") (pinfunction "D1_2") (pintype "unspecified"))
    )
    (net (code "90") (name "unconnected-(U37-D3-Pad4)") (class "Default")
      (node (ref "U37") (pin "4") (pinfunction "D3_4") (pintype "unspecified"))
    )
    (net (code "91") (name "unconnected-(U37-D4-Pad5)") (class "Default")
      (node (ref "U37") (pin "5") (pinfunction "D4_5") (pintype "unspecified"))
    )
    (net (code "92") (name "unconnected-(U37-D11-Pad12)") (class "Default")
      (node (ref "U37") (pin "12") (pinfunction "D11_12") (pintype "unspecified"))
    )
    (net (code "93") (name "unconnected-(U37-D12-Pad13)") (class "Default")
      (node (ref "U37") (pin "13") (pinfunction "D12_13") (pintype "unspecified"))
    )
    (net (code "94") (name "unconnected-(U37-D13-Pad14)") (class "Default")
      (node (ref "U37") (pin "14") (pinfunction "D13_14") (pintype "unspecified"))
    )
    (net (code "95") (name "unconnected-(U37-GND-Pad15)") (class "Default")
      (node (ref "U37") (pin "15") (pinfunction "GND_15") (pintype "passive"))
    )
    (net (code "96") (name "unconnected-(U37-GND2-Pad27)") (class "Default")
      (node (ref "U37") (pin "27") (pinfunction "GND2_27") (pintype "passive"))
    )
    (net (code "97") (name "unconnected-(U37-IOREF-Pad31)") (class "Default")
      (node (ref "U37") (pin "31") (pinfunction "IOREF_31") (pintype "unspecified"))
    )
    (net (code "98") (name "unconnected-(U37-RESET-Pad30)") (class "Default")
      (node (ref "U37") (pin "30") (pinfunction "RESET_30") (pintype "unspecified"))
    )
    (net (code "99") (name "unconnected-(U37-SCL-Pad18)") (class "Default")
      (node (ref "U37") (pin "18") (pinfunction "SCL_18") (pintype "unspecified"))
    )
    (net (code "100") (name "unconnected-(U37-SDA-Pad17)") (class "Default")
      (node (ref "U37") (pin "17") (pinfunction "SDA_17") (pintype "unspecified"))
    )
    (net (code "101") (name "unconnected-(U37-USART1-Pad32)") (class "Default")
      (node (ref "U37") (pin "32") (pinfunction "USART1_32") (pintype "unspecified"))
    )
    (net (code "102") (name "unconnected-(U47-3V-Pad29)") (class "Default")
      (node (ref "U47") (pin "29") (pinfunction "3V_29") (pintype "passive"))
    )
    (net (code "103") (name "unconnected-(U47-5V-Pad28)") (class "Default")
      (node (ref "U47") (pin "28") (pinfunction "5V_28") (pintype "passive"))
    )
    (net (code "104") (name "unconnected-(U47-A0-Pad24)") (class "Default")
      (node (ref "U47") (pin "24") (pinfunction "A0_24") (pintype "unspecified"))
    )
    (net (code "105") (name "unconnected-(U47-A1-Pad23)") (class "Default")
      (node (ref "U47") (pin "23") (pinfunction "A1_23") (pintype "unspecified"))
    )
    (net (code "106") (name "unconnected-(U47-A2-Pad22)") (class "Default")
      (node (ref "U47") (pin "22") (pinfunction "A2_22") (pintype "unspecified"))
    )
    (net (code "107") (name "unconnected-(U47-A3-Pad21)") (class "Default")
      (node (ref "U47") (pin "21") (pinfunction "A3_21") (pintype "unspecified"))
    )
    (net (code "108") (name "unconnected-(U47-A4-Pad20)") (class "Default")
      (node (ref "U47") (pin "20") (pinfunction "A4_20") (pintype "unspecified"))
    )
    (net (code "109") (name "unconnected-(U47-A5-Pad19)") (class "Default")
      (node (ref "U47") (pin "19") (pinfunction "A5_19") (pintype "unspecified"))
    )
    (net (code "110") (name "unconnected-(U47-AREF-Pad16)") (class "Default")
      (node (ref "U47") (pin "16") (pinfunction "AREF_16") (pintype "unspecified"))
    )
    (net (code "111") (name "unconnected-(U47-D0-Pad1)") (class "Default")
      (node (ref "U47") (pin "1") (pinfunction "D0_1") (pintype "unspecified"))
    )
    (net (code "112") (name "unconnected-(U47-D1-Pad2)") (class "Default")
      (node (ref "U47") (pin "2") (pinfunction "D1_2") (pintype "unspecified"))
    )
    (net (code "113") (name "unconnected-(U47-D2-Pad3)") (class "Default")
      (node (ref "U47") (pin "3") (pinfunction "D2_3") (pintype "unspecified"))
    )
    (net (code "114") (name "unconnected-(U47-D3-Pad4)") (class "Default")
      (node (ref "U47") (pin "4") (pinfunction "D3_4") (pintype "unspecified"))
    )
    (net (code "115") (name "unconnected-(U47-D4-Pad5)") (class "Default")
      (node (ref "U47") (pin "5") (pinfunction "D4_5") (pintype "unspecified"))
    )
    (net (code "116") (name "unconnected-(U47-D11-Pad12)") (class "Default")
      (node (ref "U47") (pin "12") (pinfunction "D11_12") (pintype "unspecified"))
    )
    (net (code "117") (name "unconnected-(U47-D12-Pad13)") (class "Default")
      (node (ref "U47") (pin "13") (pinfunction "D12_13") (pintype "unspecified"))
    )
    (net (code "118") (name "unconnected-(U47-D13-Pad14)") (class "Default")
      (node (ref "U47") (pin "14") (pinfunction "D13_14") (pintype "unspecified"))
    )
    (net (code "119") (name "unconnected-(U47-GND-Pad15)") (class "Default")
      (node (ref "U47") (pin "15") (pinfunction "GND_15") (pintype "passive"))
    )
    (net (code "120") (name "unconnected-(U47-GND1-Pad26)") (class "Default")
      (node (ref "U47") (pin "26") (pinfunction "GND1_26") (pintype "passive"))
    )
    (net (code "121") (name "unconnected-(U47-GND2-Pad27)") (class "Default")
      (node (ref "U47") (pin "27") (pinfunction "GND2_27") (pintype "passive"))
    )
    (net (code "122") (name "unconnected-(U47-IOREF-Pad31)") (class "Default")
      (node (ref "U47") (pin "31") (pinfunction "IOREF_31") (pintype "unspecified"))
    )
    (net (code "123") (name "unconnected-(U47-RESET-Pad30)") (class "Default")
      (node (ref "U47") (pin "30") (pinfunction "RESET_30") (pintype "unspecified"))
    )
    (net (code "124") (name "unconnected-(U47-SCL-Pad18)") (class "Default")
      (node (ref "U47") (pin "18") (pinfunction "SCL_18") (pintype "unspecified"))
    )
    (net (code "125") (name "unconnected-(U47-SDA-Pad17)") (class "Default")
      (node (ref "U47") (pin "17") (pinfunction "SDA_17") (pintype "unspecified"))
    )
    (net (code "126") (name "unconnected-(U47-USART1-Pad32)") (class "Default")
      (node (ref "U47") (pin "32") (pinfunction "USART1_32") (pintype "unspecified"))
    )
    (net (code "127") (name "unconnected-(U47-VIN-Pad25)") (class "Default")
      (node (ref "U47") (pin "25") (pinfunction "VIN_25") (pintype "passive"))
    )
    (net (code "128") (name "unconnected-(U51-3V-Pad29)") (class "Default")
      (node (ref "U51") (pin "29") (pinfunction "3V_29") (pintype "passive"))
    )
    (net (code "129") (name "unconnected-(U51-AREF-Pad16)") (class "Default")
      (node (ref "U51") (pin "16") (pinfunction "AREF_16") (pintype "unspecified"))
    )
    (net (code "130") (name "unconnected-(U51-D0-Pad1)") (class "Default")
      (node (ref "U51") (pin "1") (pinfunction "D0_1") (pintype "unspecified"))
    )
    (net (code "131") (name "unconnected-(U51-D1-Pad2)") (class "Default")
      (node (ref "U51") (pin "2") (pinfunction "D1_2") (pintype "unspecified"))
    )
    (net (code "132") (name "unconnected-(U51-D2-Pad3)") (class "Default")
      (node (ref "U51") (pin "3") (pinfunction "D2_3") (pintype "unspecified"))
    )
    (net (code "133") (name "unconnected-(U51-D3-Pad4)") (class "Default")
      (node (ref "U51") (pin "4") (pinfunction "D3_4") (pintype "unspecified"))
    )
    (net (code "134") (name "unconnected-(U51-D4-Pad5)") (class "Default")
      (node (ref "U51") (pin "5") (pinfunction "D4_5") (pintype "unspecified"))
    )
    (net (code "135") (name "unconnected-(U51-D5-Pad6)") (class "Default")
      (node (ref "U51") (pin "6") (pinfunction "D5_6") (pintype "unspecified"))
    )
    (net (code "136") (name "unconnected-(U51-D6-Pad7)") (class "Default")
      (node (ref "U51") (pin "7") (pinfunction "D6_7") (pintype "unspecified"))
    )
    (net (code "137") (name "unconnected-(U51-D7-Pad8)") (class "Default")
      (node (ref "U51") (pin "8") (pinfunction "D7_8") (pintype "unspecified"))
    )
    (net (code "138") (name "unconnected-(U51-D8-Pad9)") (class "Default")
      (node (ref "U51") (pin "9") (pinfunction "D8_9") (pintype "unspecified"))
    )
    (net (code "139") (name "unconnected-(U51-D9-Pad10)") (class "Default")
      (node (ref "U51") (pin "10") (pinfunction "D9_10") (pintype "unspecified"))
    )
    (net (code "140") (name "unconnected-(U51-D10-Pad11)") (class "Default")
      (node (ref "U51") (pin "11") (pinfunction "D10_11") (pintype "unspecified"))
    )
    (net (code "141") (name "unconnected-(U51-D11-Pad12)") (class "Default")
      (node (ref "U51") (pin "12") (pinfunction "D11_12") (pintype "unspecified"))
    )
    (net (code "142") (name "unconnected-(U51-D12-Pad13)") (class "Default")
      (node (ref "U51") (pin "13") (pinfunction "D12_13") (pintype "unspecified"))
    )
    (net (code "143") (name "unconnected-(U51-D13-Pad14)") (class "Default")
      (node (ref "U51") (pin "14") (pinfunction "D13_14") (pintype "unspecified"))
    )
    (net (code "144") (name "unconnected-(U51-GND-Pad15)") (class "Default")
      (node (ref "U51") (pin "15") (pinfunction "GND_15") (pintype "passive"))
    )
    (net (code "145") (name "unconnected-(U51-GND2-Pad27)") (class "Default")
      (node (ref "U51") (pin "27") (pinfunction "GND2_27") (pintype "passive"))
    )
    (net (code "146") (name "unconnected-(U51-IOREF-Pad31)") (class "Default")
      (node (ref "U51") (pin "31") (pinfunction "IOREF_31") (pintype "unspecified"))
    )
    (net (code "147") (name "unconnected-(U51-RESET-Pad30)") (class "Default")
      (node (ref "U51") (pin "30") (pinfunction "RESET_30") (pintype "unspecified"))
    )
    (net (code "148") (name "unconnected-(U51-SCL-Pad18)") (class "Default")
      (node (ref "U51") (pin "18") (pinfunction "SCL_18") (pintype "unspecified"))
    )
    (net (code "149") (name "unconnected-(U51-SDA-Pad17)") (class "Default")
      (node (ref "U51") (pin "17") (pinfunction "SDA_17") (pintype "unspecified"))
    )
    (net (code "150") (name "unconnected-(U51-USART1-Pad32)") (class "Default")
      (node (ref "U51") (pin "32") (pinfunction "USART1_32") (pintype "unspecified"))
    )
    (net (code "151") (name "unconnected-(U51-VIN-Pad25)") (class "Default")
      (node (ref "U51") (pin "25") (pinfunction "VIN_25") (pintype "passive"))
    )
    (net (code "152") (name "unconnected-(U52-3V-Pad29)") (class "Default")
      (node (ref "U52") (pin "29") (pinfunction "3V_29") (pintype "passive"))
    )
    (net (code "153") (name "unconnected-(U52-A0-Pad24)") (class "Default")
      (node (ref "U52") (pin "24") (pinfunction "A0_24") (pintype "unspecified"))
    )
    (net (code "154") (name "unconnected-(U52-A1-Pad23)") (class "Default")
      (node (ref "U52") (pin "23") (pinfunction "A1_23") (pintype "unspecified"))
    )
    (net (code "155") (name "unconnected-(U52-A2-Pad22)") (class "Default")
      (node (ref "U52") (pin "22") (pinfunction "A2_22") (pintype "unspecified"))
    )
    (net (code "156") (name "unconnected-(U52-A3-Pad21)") (class "Default")
      (node (ref "U52") (pin "21") (pinfunction "A3_21") (pintype "unspecified"))
    )
    (net (code "157") (name "unconnected-(U52-A4-Pad20)") (class "Default")
      (node (ref "U52") (pin "20") (pinfunction "A4_20") (pintype "unspecified"))
    )
    (net (code "158") (name "unconnected-(U52-A5-Pad19)") (class "Default")
      (node (ref "U52") (pin "19") (pinfunction "A5_19") (pintype "unspecified"))
    )
    (net (code "159") (name "unconnected-(U52-AREF-Pad16)") (class "Default")
      (node (ref "U52") (pin "16") (pinfunction "AREF_16") (pintype "unspecified"))
    )
    (net (code "160") (name "unconnected-(U52-D1-Pad2)") (class "Default")
      (node (ref "U52") (pin "2") (pinfunction "D1_2") (pintype "unspecified"))
    )
    (net (code "161") (name "unconnected-(U52-D2-Pad3)") (class "Default")
      (node (ref "U52") (pin "3") (pinfunction "D2_3") (pintype "unspecified"))
    )
    (net (code "162") (name "unconnected-(U52-D3-Pad4)") (class "Default")
      (node (ref "U52") (pin "4") (pinfunction "D3_4") (pintype "unspecified"))
    )
    (net (code "163") (name "unconnected-(U52-D4-Pad5)") (class "Default")
      (node (ref "U52") (pin "5") (pinfunction "D4_5") (pintype "unspecified"))
    )
    (net (code "164") (name "unconnected-(U52-D5-Pad6)") (class "Default")
      (node (ref "U52") (pin "6") (pinfunction "D5_6") (pintype "unspecified"))
    )
    (net (code "165") (name "unconnected-(U52-D6-Pad7)") (class "Default")
      (node (ref "U52") (pin "7") (pinfunction "D6_7") (pintype "unspecified"))
    )
    (net (code "166") (name "unconnected-(U52-D7-Pad8)") (class "Default")
      (node (ref "U52") (pin "8") (pinfunction "D7_8") (pintype "unspecified"))
    )
    (net (code "167") (name "unconnected-(U52-D8-Pad9)") (class "Default")
      (node (ref "U52") (pin "9") (pinfunction "D8_9") (pintype "unspecified"))
    )
    (net (code "168") (name "unconnected-(U52-D9-Pad10)") (class "Default")
      (node (ref "U52") (pin "10") (pinfunction "D9_10") (pintype "unspecified"))
    )
    (net (code "169") (name "unconnected-(U52-D10-Pad11)") (class "Default")
      (node (ref "U52") (pin "11") (pinfunction "D10_11") (pintype "unspecified"))
    )
    (net (code "170") (name "unconnected-(U52-D11-Pad12)") (class "Default")
      (node (ref "U52") (pin "12") (pinfunction "D11_12") (pintype "unspecified"))
    )
    (net (code "171") (name "unconnected-(U52-D12-Pad13)") (class "Default")
      (node (ref "U52") (pin "13") (pinfunction "D12_13") (pintype "unspecified"))
    )
    (net (code "172") (name "unconnected-(U52-D13-Pad14)") (class "Default")
      (node (ref "U52") (pin "14") (pinfunction "D13_14") (pintype "unspecified"))
    )
    (net (code "173") (name "unconnected-(U52-GND-Pad15)") (class "Default")
      (node (ref "U52") (pin "15") (pinfunction "GND_15") (pintype "passive"))
    )
    (net (code "174") (name "unconnected-(U52-GND2-Pad27)") (class "Default")
      (node (ref "U52") (pin "27") (pinfunction "GND2_27") (pintype "passive"))
    )
    (net (code "175") (name "unconnected-(U52-IOREF-Pad31)") (class "Default")
      (node (ref "U52") (pin "31") (pinfunction "IOREF_31") (pintype "unspecified"))
    )
    (net (code "176") (name "unconnected-(U52-RESET-Pad30)") (class "Default")
      (node (ref "U52") (pin "30") (pinfunction "RESET_30") (pintype "unspecified"))
    )
    (net (code "177") (name "unconnected-(U52-SCL-Pad18)") (class "Default")
      (node (ref "U52") (pin "18") (pinfunction "SCL_18") (pintype "unspecified"))
    )
    (net (code "178") (name "unconnected-(U52-SDA-Pad17)") (class "Default")
      (node (ref "U52") (pin "17") (pinfunction "SDA_17") (pintype "unspecified"))
    )
    (net (code "179") (name "unconnected-(U52-USART1-Pad32)") (class "Default")
      (node (ref "U52") (pin "32") (pinfunction "USART1_32") (pintype "unspecified"))
    )
    (net (code "180") (name "unconnected-(U52-VIN-Pad25)") (class "Default")
      (node (ref "U52") (pin "25") (pinfunction "VIN_25") (pintype "passive"))
    )
    (net (code "181") (name "unconnected-(U53-D1-Pad9)") (class "Default")
      (node (ref "U53") (pin "9") (pinfunction "D1_9") (pintype "unspecified"))
    )
    (net (code "182") (name "unconnected-(U53-D2-Pad10)") (class "Default")
      (node (ref "U53") (pin "10") (pinfunction "D2_10") (pintype "unspecified"))
    )
    (net (code "183") (name "unconnected-(U53-NC-Pad2)") (class "Default")
      (node (ref "U53") (pin "2") (pinfunction "NC_2") (pintype "unspecified"))
    )
    (net (code "184") (name "unconnected-(U53-NC-Pad5)") (class "Default")
      (node (ref "U53") (pin "5") (pinfunction "NC_5") (pintype "unspecified"))
    )
    (net (code "185") (name "unconnected-(U53-NC-Pad6)") (class "Default")
      (node (ref "U53") (pin "6") (pinfunction "NC_6") (pintype "unspecified"))
    )
    (net (code "186") (name "unconnected-(U54-3V-Pad29)") (class "Default")
      (node (ref "U54") (pin "29") (pinfunction "3V_29") (pintype "passive"))
    )
    (net (code "187") (name "unconnected-(U54-A0-Pad24)") (class "Default")
      (node (ref "U54") (pin "24") (pinfunction "A0_24") (pintype "unspecified"))
    )
    (net (code "188") (name "unconnected-(U54-A1-Pad23)") (class "Default")
      (node (ref "U54") (pin "23") (pinfunction "A1_23") (pintype "unspecified"))
    )
    (net (code "189") (name "unconnected-(U54-A2-Pad22)") (class "Default")
      (node (ref "U54") (pin "22") (pinfunction "A2_22") (pintype "unspecified"))
    )
    (net (code "190") (name "unconnected-(U54-A3-Pad21)") (class "Default")
      (node (ref "U54") (pin "21") (pinfunction "A3_21") (pintype "unspecified"))
    )
    (net (code "191") (name "unconnected-(U54-A4-Pad20)") (class "Default")
      (node (ref "U54") (pin "20") (pinfunction "A4_20") (pintype "unspecified"))
    )
    (net (code "192") (name "unconnected-(U54-A5-Pad19)") (class "Default")
      (node (ref "U54") (pin "19") (pinfunction "A5_19") (pintype "unspecified"))
    )
    (net (code "193") (name "unconnected-(U54-AREF-Pad16)") (class "Default")
      (node (ref "U54") (pin "16") (pinfunction "AREF_16") (pintype "unspecified"))
    )
    (net (code "194") (name "unconnected-(U54-D0-Pad1)") (class "Default")
      (node (ref "U54") (pin "1") (pinfunction "D0_1") (pintype "unspecified"))
    )
    (net (code "195") (name "unconnected-(U54-D1-Pad2)") (class "Default")
      (node (ref "U54") (pin "2") (pinfunction "D1_2") (pintype "unspecified"))
    )
    (net (code "196") (name "unconnected-(U54-D3-Pad4)") (class "Default")
      (node (ref "U54") (pin "4") (pinfunction "D3_4") (pintype "unspecified"))
    )
    (net (code "197") (name "unconnected-(U54-D4-Pad5)") (class "Default")
      (node (ref "U54") (pin "5") (pinfunction "D4_5") (pintype "unspecified"))
    )
    (net (code "198") (name "unconnected-(U54-D5-Pad6)") (class "Default")
      (node (ref "U54") (pin "6") (pinfunction "D5_6") (pintype "unspecified"))
    )
    (net (code "199") (name "unconnected-(U54-D6-Pad7)") (class "Default")
      (node (ref "U54") (pin "7") (pinfunction "D6_7") (pintype "unspecified"))
    )
    (net (code "200") (name "unconnected-(U54-D7-Pad8)") (class "Default")
      (node (ref "U54") (pin "8") (pinfunction "D7_8") (pintype "unspecified"))
    )
    (net (code "201") (name "unconnected-(U54-D8-Pad9)") (class "Default")
      (node (ref "U54") (pin "9") (pinfunction "D8_9") (pintype "unspecified"))
    )
    (net (code "202") (name "unconnected-(U54-D9-Pad10)") (class "Default")
      (node (ref "U54") (pin "10") (pinfunction "D9_10") (pintype "unspecified"))
    )
    (net (code "203") (name "unconnected-(U54-D10-Pad11)") (class "Default")
      (node (ref "U54") (pin "11") (pinfunction "D10_11") (pintype "unspecified"))
    )
    (net (code "204") (name "unconnected-(U54-D11-Pad12)") (class "Default")
      (node (ref "U54") (pin "12") (pinfunction "D11_12") (pintype "unspecified"))
    )
    (net (code "205") (name "unconnected-(U54-D12-Pad13)") (class "Default")
      (node (ref "U54") (pin "13") (pinfunction "D12_13") (pintype "unspecified"))
    )
    (net (code "206") (name "unconnected-(U54-D13-Pad14)") (class "Default")
      (node (ref "U54") (pin "14") (pinfunction "D13_14") (pintype "unspecified"))
    )
    (net (code "207") (name "unconnected-(U54-GND-Pad15)") (class "Default")
      (node (ref "U54") (pin "15") (pinfunction "GND_15") (pintype "passive"))
    )
    (net (code "208") (name "unconnected-(U54-GND2-Pad27)") (class "Default")
      (node (ref "U54") (pin "27") (pinfunction "GND2_27") (pintype "passive"))
    )
    (net (code "209") (name "unconnected-(U54-IOREF-Pad31)") (class "Default")
      (node (ref "U54") (pin "31") (pinfunction "IOREF_31") (pintype "unspecified"))
    )
    (net (code "210") (name "unconnected-(U54-RESET-Pad30)") (class "Default")
      (node (ref "U54") (pin "30") (pinfunction "RESET_30") (pintype "unspecified"))
    )
    (net (code "211") (name "unconnected-(U54-SCL-Pad18)") (class "Default")
      (node (ref "U54") (pin "18") (pinfunction "SCL_18") (pintype "unspecified"))
    )
    (net (code "212") (name "unconnected-(U54-SDA-Pad17)") (class "Default")
      (node (ref "U54") (pin "17") (pinfunction "SDA_17") (pintype "unspecified"))
    )
    (net (code "213") (name "unconnected-(U54-USART1-Pad32)") (class "Default")
      (node (ref "U54") (pin "32") (pinfunction "USART1_32") (pintype "unspecified"))
    )
    (net (code "214") (name "unconnected-(U55-NO-Pad5)") (class "Default")
      (node (ref "U55") (pin "5") (pinfunction "NO_5") (pintype "unspecified"))
    )
  )
)
